# BelaCore.net
KiCad netlist of a schematic drawn in EAGLE
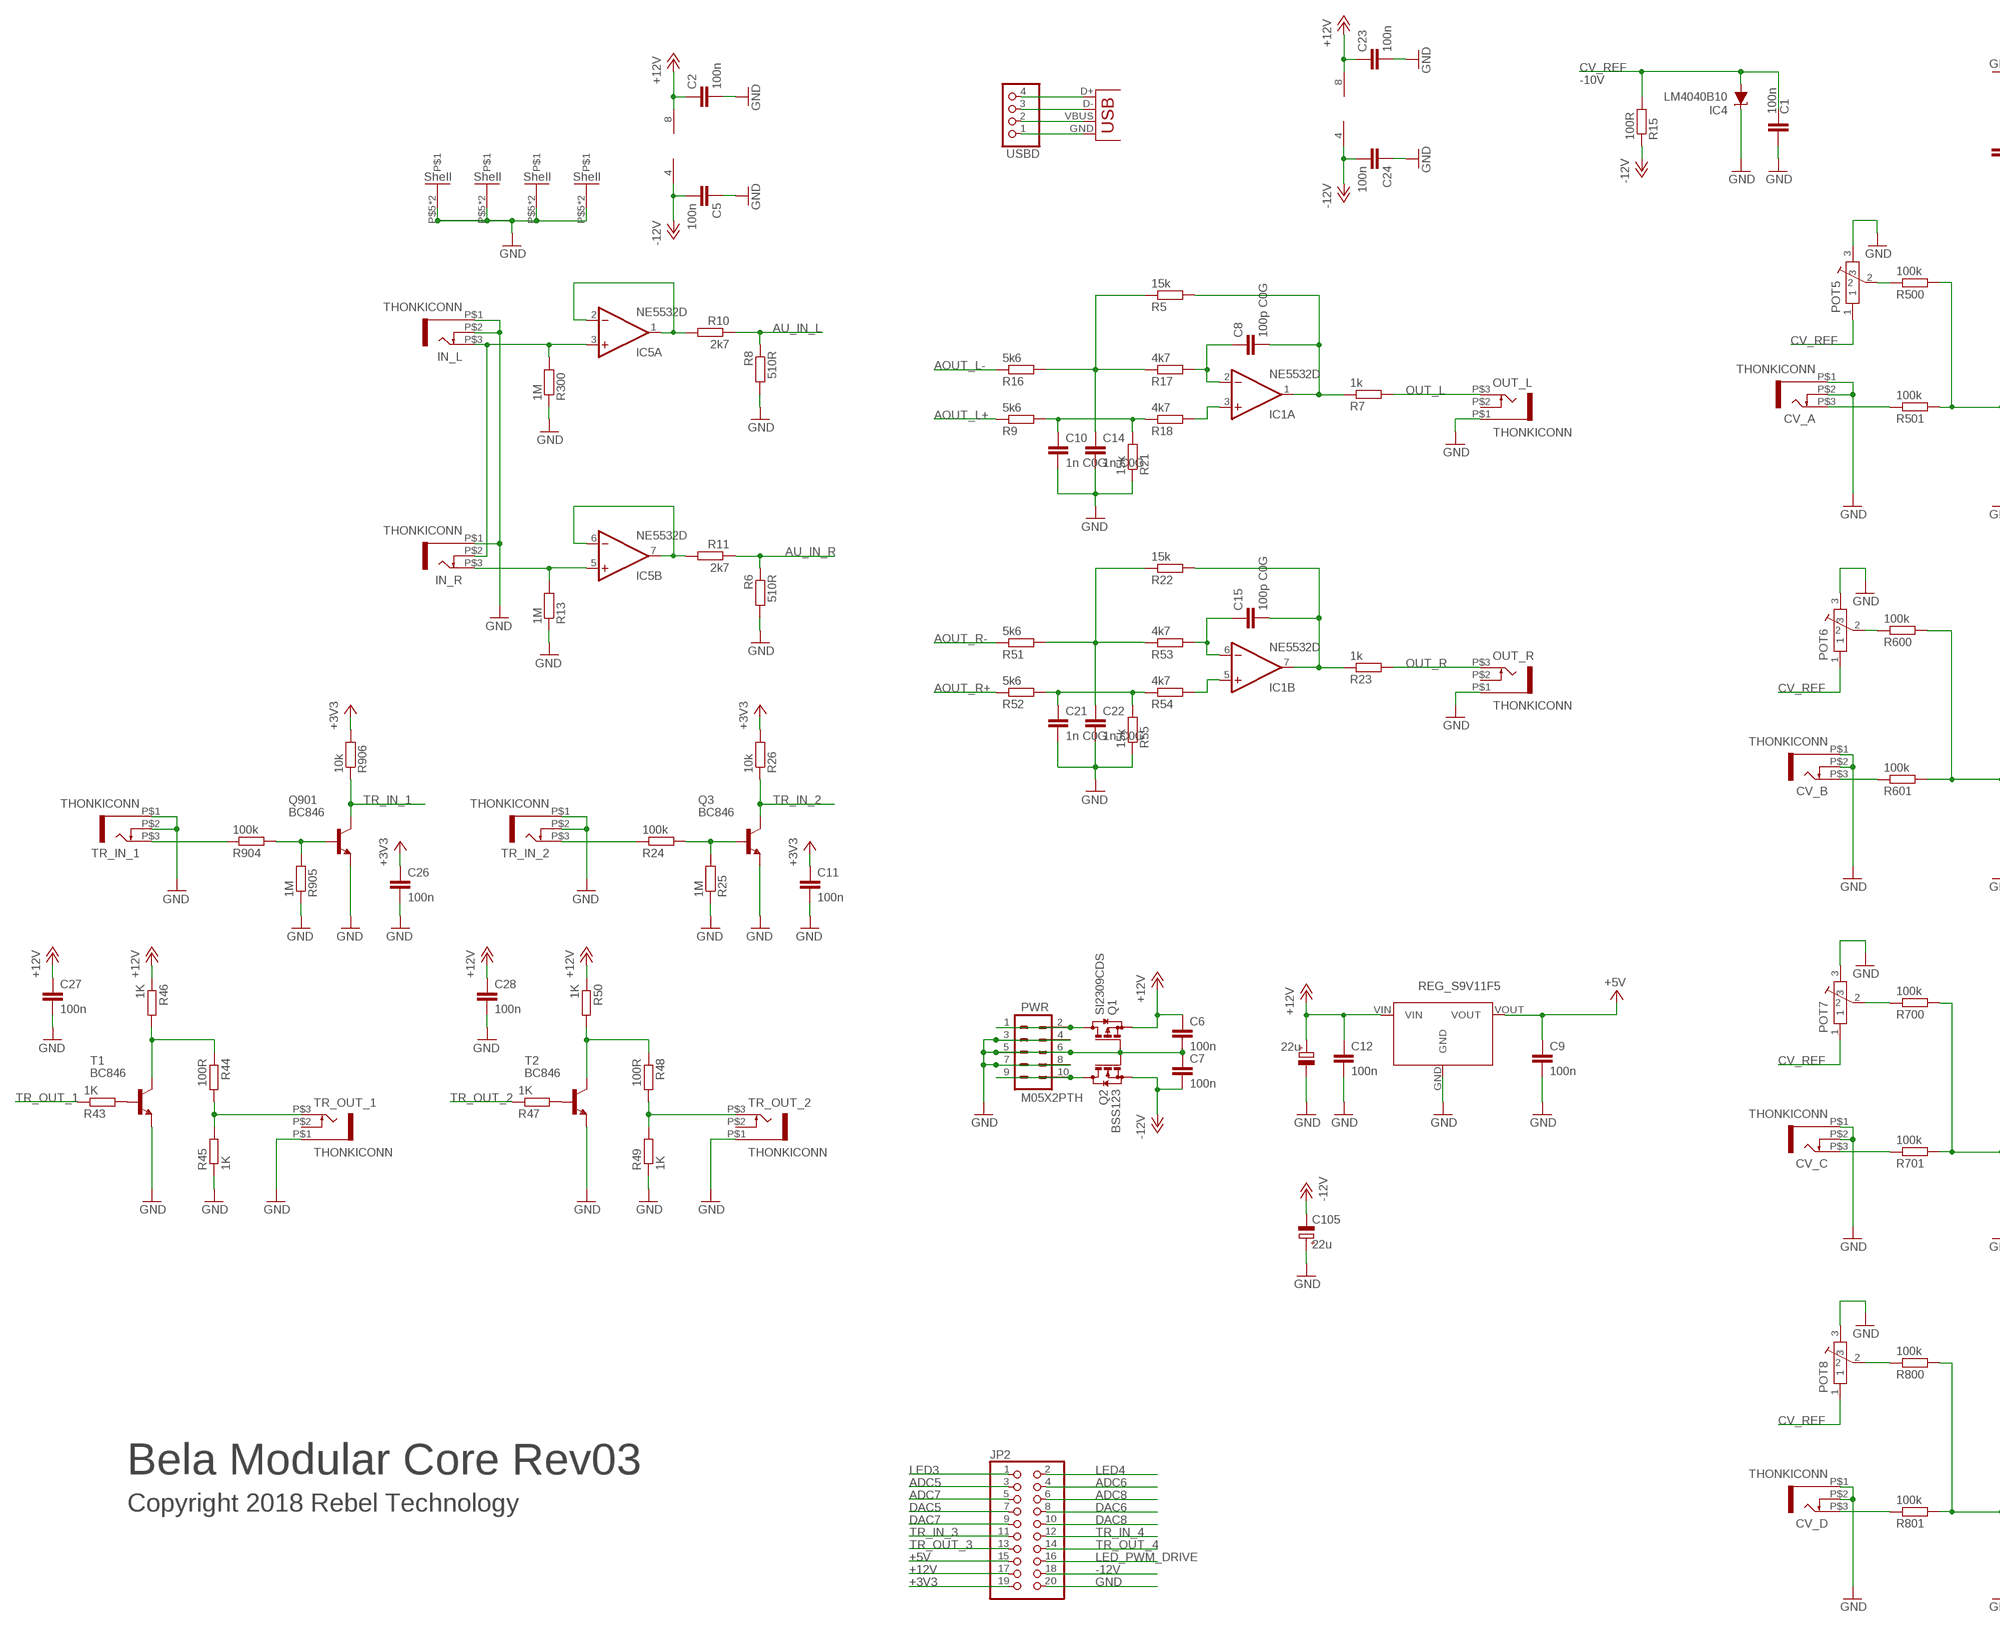
[diagram p0: schematic, sheet 1, part 1 of 2]
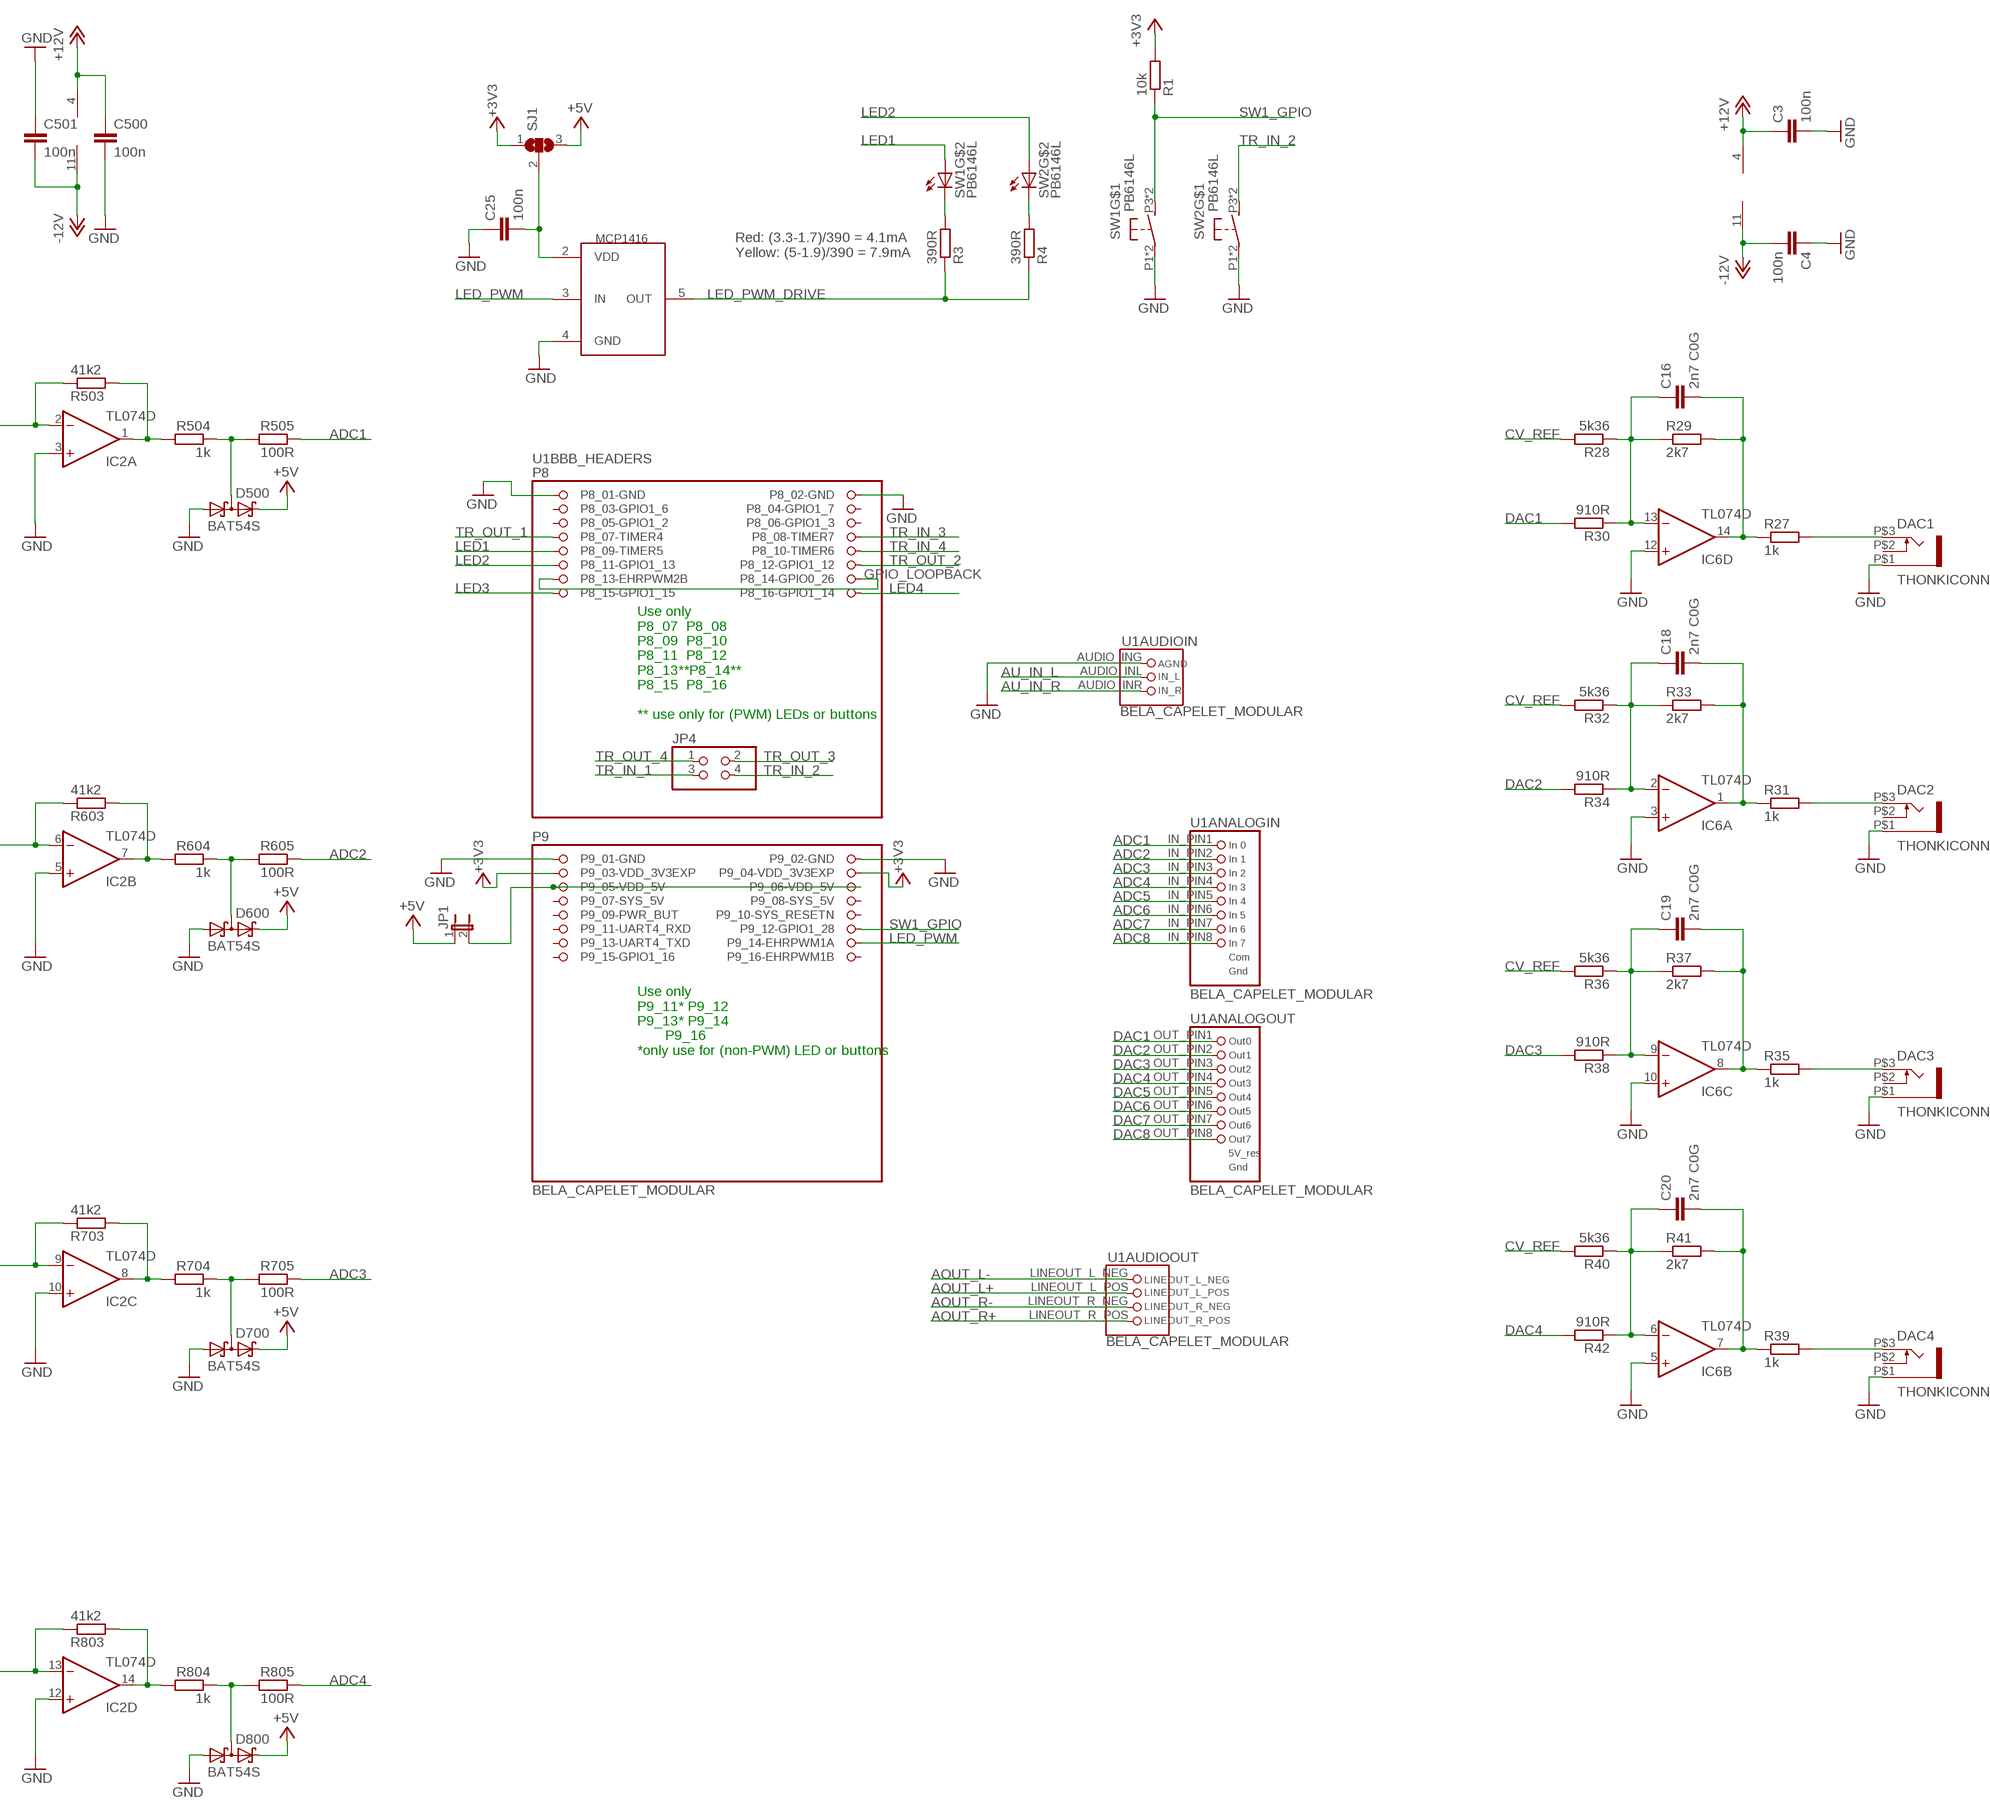
[diagram p1: schematic, sheet 1, part 2 of 2]

(export (version "E")
  (design (tool "Eeschema 10.0.6"))
  (components
    (comp (ref "C1")
      (value "100n")
      (footprint "eagle-import:C0603")
      (libsource (lib "eagle-import") (part "resistor_C-EUC0603"))
    )
    (comp (ref "C2")
      (value "100n")
      (footprint "eagle-import:C0603")
      (libsource (lib "eagle-import") (part "resistor_C-EUC0603"))
    )
    (comp (ref "C3")
      (value "100n")
      (footprint "eagle-import:C0603")
      (libsource (lib "eagle-import") (part "resistor_C-EUC0603"))
    )
    (comp (ref "C4")
      (value "100n")
      (footprint "eagle-import:C0603")
      (libsource (lib "eagle-import") (part "resistor_C-EUC0603"))
    )
    (comp (ref "C5")
      (value "100n")
      (footprint "eagle-import:C0603")
      (libsource (lib "eagle-import") (part "resistor_C-EUC0603"))
    )
    (comp (ref "C6")
      (value "100n")
      (footprint "eagle-import:C0603")
      (libsource (lib "eagle-import") (part "resistor_C-EUC0603"))
    )
    (comp (ref "C7")
      (value "100n")
      (footprint "eagle-import:C0603")
      (libsource (lib "eagle-import") (part "resistor_C-EUC0603"))
    )
    (comp (ref "C8")
      (value "100p C0G")
      (footprint "eagle-import:C0603")
      (libsource (lib "eagle-import") (part "resistor_C-EUC0603"))
    )
    (comp (ref "C9")
      (value "100n")
      (footprint "eagle-import:C0603")
      (libsource (lib "eagle-import") (part "C-EUC0603"))
    )
    (comp (ref "C10")
      (value "1n C0G")
      (footprint "eagle-import:C0603")
      (libsource (lib "eagle-import") (part "resistor_C-EUC0603"))
    )
    (comp (ref "C11")
      (value "100n")
      (footprint "eagle-import:C0603")
      (libsource (lib "eagle-import") (part "resistor_C-EUC0603"))
    )
    (comp (ref "C12")
      (value "100n")
      (footprint "eagle-import:C0603")
      (libsource (lib "eagle-import") (part "C-EUC0603"))
    )
    (comp (ref "C14")
      (value "1n C0G")
      (footprint "eagle-import:C0603")
      (libsource (lib "eagle-import") (part "resistor_C-EUC0603"))
    )
    (comp (ref "C15")
      (value "100p C0G")
      (footprint "eagle-import:C0603")
      (libsource (lib "eagle-import") (part "resistor_C-EUC0603"))
    )
    (comp (ref "C16")
      (value "2n7 C0G")
      (footprint "eagle-import:C0603")
      (libsource (lib "eagle-import") (part "C-EUC0603"))
    )
    (comp (ref "C17")
      (value "22u")
      (footprint "eagle-import:CPOL-5")
      (libsource (lib "eagle-import") (part "CPOL-EU153CLV-0505"))
    )
    (comp (ref "C18")
      (value "2n7 C0G")
      (footprint "eagle-import:C0603")
      (libsource (lib "eagle-import") (part "C-EUC0603"))
    )
    (comp (ref "C19")
      (value "2n7 C0G")
      (footprint "eagle-import:C0603")
      (libsource (lib "eagle-import") (part "C-EUC0603"))
    )
    (comp (ref "C20")
      (value "2n7 C0G")
      (footprint "eagle-import:C0603")
      (libsource (lib "eagle-import") (part "C-EUC0603"))
    )
    (comp (ref "C21")
      (value "1n C0G")
      (footprint "eagle-import:C0603")
      (libsource (lib "eagle-import") (part "resistor_C-EUC0603"))
    )
    (comp (ref "C22")
      (value "1n C0G")
      (footprint "eagle-import:C0603")
      (libsource (lib "eagle-import") (part "resistor_C-EUC0603"))
    )
    (comp (ref "C23")
      (value "100n")
      (footprint "eagle-import:C0603")
      (libsource (lib "eagle-import") (part "resistor_C-EUC0603"))
    )
    (comp (ref "C24")
      (value "100n")
      (footprint "eagle-import:C0603")
      (libsource (lib "eagle-import") (part "resistor_C-EUC0603"))
    )
    (comp (ref "C25")
      (value "100n")
      (footprint "eagle-import:C0603")
      (libsource (lib "eagle-import") (part "C-EUC0603"))
    )
    (comp (ref "C26")
      (value "100n")
      (footprint "eagle-import:C0603")
      (libsource (lib "eagle-import") (part "resistor_C-EUC0603"))
    )
    (comp (ref "C27")
      (value "100n")
      (footprint "eagle-import:C0603")
      (libsource (lib "eagle-import") (part "resistor_C-EUC0603"))
    )
    (comp (ref "C28")
      (value "100n")
      (footprint "eagle-import:C0603")
      (libsource (lib "eagle-import") (part "resistor_C-EUC0603"))
    )
    (comp (ref "C105")
      (value "22u")
      (footprint "eagle-import:CPOL-5")
      (libsource (lib "eagle-import") (part "CPOL-EU153CLV-0505"))
    )
    (comp (ref "C500")
      (value "100n")
      (footprint "eagle-import:C0603")
      (libsource (lib "eagle-import") (part "resistor_C-EUC0603"))
    )
    (comp (ref "C501")
      (value "100n")
      (footprint "eagle-import:C0603")
      (libsource (lib "eagle-import") (part "resistor_C-EUC0603"))
    )
    (comp (ref "CV_A")
      (value "THONKICONN")
      (footprint "eagle-import:THONKICONN")
      (libsource (lib "eagle-import") (part "THONKICONN"))
    )
    (comp (ref "CV_B")
      (value "THONKICONN")
      (footprint "eagle-import:THONKICONN")
      (libsource (lib "eagle-import") (part "THONKICONN"))
    )
    (comp (ref "CV_C")
      (value "THONKICONN")
      (footprint "eagle-import:THONKICONN")
      (libsource (lib "eagle-import") (part "THONKICONN"))
    )
    (comp (ref "CV_D")
      (value "THONKICONN")
      (footprint "eagle-import:THONKICONN")
      (libsource (lib "eagle-import") (part "THONKICONN"))
    )
    (comp (ref "D500")
      (value "BAT54S")
      (footprint "eagle-import:SOT23")
      (libsource (lib "eagle-import") (part "BAT54S"))
    )
    (comp (ref "D600")
      (value "BAT54S")
      (footprint "eagle-import:SOT23")
      (libsource (lib "eagle-import") (part "BAT54S"))
    )
    (comp (ref "D700")
      (value "BAT54S")
      (footprint "eagle-import:SOT23")
      (libsource (lib "eagle-import") (part "BAT54S"))
    )
    (comp (ref "D800")
      (value "BAT54S")
      (footprint "eagle-import:SOT23")
      (libsource (lib "eagle-import") (part "BAT54S"))
    )
    (comp (ref "DAC1")
      (value "THONKICONN")
      (footprint "eagle-import:THONKICONN")
      (libsource (lib "eagle-import") (part "THONKICONN"))
    )
    (comp (ref "DAC2")
      (value "THONKICONN")
      (footprint "eagle-import:THONKICONN")
      (libsource (lib "eagle-import") (part "THONKICONN"))
    )
    (comp (ref "DAC3")
      (value "THONKICONN")
      (footprint "eagle-import:THONKICONN")
      (libsource (lib "eagle-import") (part "THONKICONN"))
    )
    (comp (ref "DAC4")
      (value "THONKICONN")
      (footprint "eagle-import:THONKICONN")
      (libsource (lib "eagle-import") (part "THONKICONN"))
    )
    (comp (ref "IC1")
      (value "NE5532D")
      (footprint "eagle-import:SO08")
      (libsource (lib "eagle-import") (part "NE5532D"))
    )
    (comp (ref "IC2")
      (value "TL074D")
      (footprint "eagle-import:SO14")
      (libsource (lib "eagle-import") (part "TL074D"))
    )
    (comp (ref "IC4")
      (value "LM4040B10")
      (footprint "eagle-import:DBZ_R-PDSO-G3")
      (fields (field (name "MF") "TEXAS INSTRUMENT CONNECTORS") (field (name "MPN") "LM4041C12QDBZT"))
      (libsource (lib "eagle-import") (part "LM4041DBZC12"))
    )
    (comp (ref "IC5")
      (value "NE5532D")
      (footprint "eagle-import:SO08")
      (libsource (lib "eagle-import") (part "NE5532D"))
    )
    (comp (ref "IC6")
      (value "TL074D")
      (footprint "eagle-import:SO14")
      (libsource (lib "eagle-import") (part "TL074D"))
    )
    (comp (ref "IN_L")
      (value "THONKICONN")
      (footprint "eagle-import:THONKICONN")
      (libsource (lib "eagle-import") (part "THONKICONN"))
    )
    (comp (ref "IN_R")
      (value "THONKICONN")
      (footprint "eagle-import:THONKICONN")
      (libsource (lib "eagle-import") (part "THONKICONN"))
    )
    (comp (ref "JP1")
      (value "JUMPER-2PTH")
      (footprint "eagle-import:1X02")
      (libsource (lib "eagle-import") (part "JUMPER-2PTH"))
    )
    (comp (ref "JP2")
      (value "PINHD-2X10")
      (footprint "eagle-import:2X10")
      (libsource (lib "eagle-import") (part "PINHD-2X10"))
    )
    (comp (ref "JP4")
      (value "PINHD-2X02_2.54-SMD")
      (footprint "eagle-import:2X02SMD")
      (libsource (lib "eagle-import") (part "PINHD-2X02_2.54-SMD"))
    )
    (comp (ref "OUT_L")
      (value "THONKICONN")
      (footprint "eagle-import:THONKICONN")
      (libsource (lib "eagle-import") (part "THONKICONN"))
    )
    (comp (ref "OUT_R")
      (value "THONKICONN")
      (footprint "eagle-import:THONKICONN")
      (libsource (lib "eagle-import") (part "THONKICONN"))
    )
    (comp (ref "POT5")
      (value "POT-ALPS-RK09L1140")
      (footprint "eagle-import:POT-ALPS-RK09L1140")
      (libsource (lib "eagle-import") (part "POT-ALPS-RK09L1140"))
    )
    (comp (ref "POT6")
      (value "POT-ALPS-RK09L1140")
      (footprint "eagle-import:POT-ALPS-RK09L1140")
      (libsource (lib "eagle-import") (part "POT-ALPS-RK09L1140"))
    )
    (comp (ref "POT7")
      (value "POT-ALPS-RK09L1140")
      (footprint "eagle-import:POT-ALPS-RK09L1140")
      (libsource (lib "eagle-import") (part "POT-ALPS-RK09L1140"))
    )
    (comp (ref "POT8")
      (value "POT-ALPS-RK09L1140")
      (footprint "eagle-import:POT-ALPS-RK09L1140")
      (libsource (lib "eagle-import") (part "POT-ALPS-RK09L1140"))
    )
    (comp (ref "PWR")
      (value "M05X2PTH")
      (footprint "eagle-import:AVR_ICSP")
      (libsource (lib "eagle-import") (part "M05X2PTH"))
    )
    (comp (ref "Q1")
      (value "SI2309CDS")
      (footprint "eagle-import:SOT23")
      (libsource (lib "eagle-import") (part "BSS84"))
    )
    (comp (ref "Q2")
      (value "BSS123")
      (footprint "eagle-import:SOT23")
      (libsource (lib "eagle-import") (part "BSS123"))
    )
    (comp (ref "Q3")
      (value "BC846")
      (footprint "eagle-import:SOT23")
      (libsource (lib "eagle-import") (part "BC846"))
    )
    (comp (ref "Q901")
      (value "BC846")
      (footprint "eagle-import:SOT23")
      (libsource (lib "eagle-import") (part "BC846"))
    )
    (comp (ref "R1")
      (value "10k")
      (footprint "eagle-import:0603")
      (libsource (lib "eagle-import") (part "R-EU_0603"))
    )
    (comp (ref "R3")
      (value "390R")
      (footprint "eagle-import:0603")
      (libsource (lib "eagle-import") (part "R-EU_0603"))
    )
    (comp (ref "R4")
      (value "390R")
      (footprint "eagle-import:0603")
      (libsource (lib "eagle-import") (part "R-EU_0603"))
    )
    (comp (ref "R5")
      (value "15k")
      (footprint "eagle-import:0603")
      (libsource (lib "eagle-import") (part "R-EU_0603"))
    )
    (comp (ref "R6")
      (value "510R")
      (footprint "eagle-import:0603")
      (libsource (lib "eagle-import") (part "R-EU_0603"))
    )
    (comp (ref "R7")
      (value "1k")
      (footprint "eagle-import:0603")
      (libsource (lib "eagle-import") (part "R-EU_0603"))
    )
    (comp (ref "R8")
      (value "510R")
      (footprint "eagle-import:0603")
      (libsource (lib "eagle-import") (part "R-EU_0603"))
    )
    (comp (ref "R9")
      (value "5k6")
      (footprint "eagle-import:0603")
      (libsource (lib "eagle-import") (part "R-EU_0603"))
    )
    (comp (ref "R10")
      (value "2k7")
      (footprint "eagle-import:0603")
      (libsource (lib "eagle-import") (part "R-EU_0603"))
    )
    (comp (ref "R11")
      (value "2k7")
      (footprint "eagle-import:0603")
      (libsource (lib "eagle-import") (part "R-EU_0603"))
    )
    (comp (ref "R13")
      (value "1M")
      (footprint "eagle-import:0603")
      (libsource (lib "eagle-import") (part "R-EU_0603"))
    )
    (comp (ref "R15")
      (value "100R")
      (footprint "eagle-import:0603")
      (libsource (lib "eagle-import") (part "R-EU_0603"))
    )
    (comp (ref "R16")
      (value "5k6")
      (footprint "eagle-import:0603")
      (libsource (lib "eagle-import") (part "R-EU_0603"))
    )
    (comp (ref "R17")
      (value "4k7")
      (footprint "eagle-import:0603")
      (libsource (lib "eagle-import") (part "R-EU_0603"))
    )
    (comp (ref "R18")
      (value "4k7")
      (footprint "eagle-import:0603")
      (libsource (lib "eagle-import") (part "R-EU_0603"))
    )
    (comp (ref "R21")
      (value "15k")
      (footprint "eagle-import:0603")
      (libsource (lib "eagle-import") (part "R-EU_0603"))
    )
    (comp (ref "R22")
      (value "15k")
      (footprint "eagle-import:0603")
      (libsource (lib "eagle-import") (part "R-EU_0603"))
    )
    (comp (ref "R23")
      (value "1k")
      (footprint "eagle-import:0603")
      (libsource (lib "eagle-import") (part "R-EU_0603"))
    )
    (comp (ref "R24")
      (value "100k")
      (footprint "eagle-import:0603")
      (libsource (lib "eagle-import") (part "R-EU_0603"))
    )
    (comp (ref "R25")
      (value "1M")
      (footprint "eagle-import:0603")
      (libsource (lib "eagle-import") (part "R-EU_0603"))
    )
    (comp (ref "R26")
      (value "10k")
      (footprint "eagle-import:0603")
      (libsource (lib "eagle-import") (part "R-EU_0603"))
    )
    (comp (ref "R27")
      (value "1k")
      (footprint "eagle-import:0603")
      (libsource (lib "eagle-import") (part "R-EU_0603"))
    )
    (comp (ref "R28")
      (value "5k36")
      (footprint "eagle-import:0603")
      (libsource (lib "eagle-import") (part "R-EU_0603"))
    )
    (comp (ref "R29")
      (value "2k7")
      (footprint "eagle-import:0603")
      (libsource (lib "eagle-import") (part "R-EU_0603"))
    )
    (comp (ref "R30")
      (value "910R")
      (footprint "eagle-import:0603")
      (libsource (lib "eagle-import") (part "R-EU_0603"))
    )
    (comp (ref "R31")
      (value "1k")
      (footprint "eagle-import:0603")
      (libsource (lib "eagle-import") (part "R-EU_0603"))
    )
    (comp (ref "R32")
      (value "5k36")
      (footprint "eagle-import:0603")
      (libsource (lib "eagle-import") (part "R-EU_0603"))
    )
    (comp (ref "R33")
      (value "2k7")
      (footprint "eagle-import:0603")
      (libsource (lib "eagle-import") (part "R-EU_0603"))
    )
    (comp (ref "R34")
      (value "910R")
      (footprint "eagle-import:0603")
      (libsource (lib "eagle-import") (part "R-EU_0603"))
    )
    (comp (ref "R35")
      (value "1k")
      (footprint "eagle-import:0603")
      (libsource (lib "eagle-import") (part "R-EU_0603"))
    )
    (comp (ref "R36")
      (value "5k36")
      (footprint "eagle-import:0603")
      (libsource (lib "eagle-import") (part "R-EU_0603"))
    )
    (comp (ref "R37")
      (value "2k7")
      (footprint "eagle-import:0603")
      (libsource (lib "eagle-import") (part "R-EU_0603"))
    )
    (comp (ref "R38")
      (value "910R")
      (footprint "eagle-import:0603")
      (libsource (lib "eagle-import") (part "R-EU_0603"))
    )
    (comp (ref "R39")
      (value "1k")
      (footprint "eagle-import:0603")
      (libsource (lib "eagle-import") (part "R-EU_0603"))
    )
    (comp (ref "R40")
      (value "5k36")
      (footprint "eagle-import:0603")
      (libsource (lib "eagle-import") (part "R-EU_0603"))
    )
    (comp (ref "R41")
      (value "2k7")
      (footprint "eagle-import:0603")
      (libsource (lib "eagle-import") (part "R-EU_0603"))
    )
    (comp (ref "R42")
      (value "910R")
      (footprint "eagle-import:0603")
      (libsource (lib "eagle-import") (part "R-EU_0603"))
    )
    (comp (ref "R43")
      (value "1K")
      (footprint "eagle-import:0603")
      (libsource (lib "eagle-import") (part "R-EU_0603"))
    )
    (comp (ref "R44")
      (value "100R")
      (footprint "eagle-import:0603")
      (libsource (lib "eagle-import") (part "R-EU_0603"))
    )
    (comp (ref "R45")
      (value "1K")
      (footprint "eagle-import:0603")
      (libsource (lib "eagle-import") (part "R-EU_0603"))
    )
    (comp (ref "R46")
      (value "1K")
      (footprint "eagle-import:0603")
      (libsource (lib "eagle-import") (part "R-EU_0603"))
    )
    (comp (ref "R47")
      (value "1K")
      (footprint "eagle-import:0603")
      (libsource (lib "eagle-import") (part "R-EU_0603"))
    )
    (comp (ref "R48")
      (value "100R")
      (footprint "eagle-import:0603")
      (libsource (lib "eagle-import") (part "R-EU_0603"))
    )
    (comp (ref "R49")
      (value "1K")
      (footprint "eagle-import:0603")
      (libsource (lib "eagle-import") (part "R-EU_0603"))
    )
    (comp (ref "R50")
      (value "1K")
      (footprint "eagle-import:0603")
      (libsource (lib "eagle-import") (part "R-EU_0603"))
    )
    (comp (ref "R51")
      (value "5k6")
      (footprint "eagle-import:0603")
      (libsource (lib "eagle-import") (part "R-EU_0603"))
    )
    (comp (ref "R52")
      (value "5k6")
      (footprint "eagle-import:0603")
      (libsource (lib "eagle-import") (part "R-EU_0603"))
    )
    (comp (ref "R53")
      (value "4k7")
      (footprint "eagle-import:0603")
      (libsource (lib "eagle-import") (part "R-EU_0603"))
    )
    (comp (ref "R54")
      (value "4k7")
      (footprint "eagle-import:0603")
      (libsource (lib "eagle-import") (part "R-EU_0603"))
    )
    (comp (ref "R55")
      (value "15k")
      (footprint "eagle-import:0603")
      (libsource (lib "eagle-import") (part "R-EU_0603"))
    )
    (comp (ref "R300")
      (value "1M")
      (footprint "eagle-import:0603")
      (libsource (lib "eagle-import") (part "R-EU_0603"))
    )
    (comp (ref "R500")
      (value "100k")
      (footprint "eagle-import:0603")
      (libsource (lib "eagle-import") (part "R-EU_0603"))
    )
    (comp (ref "R501")
      (value "100k")
      (footprint "eagle-import:0603")
      (libsource (lib "eagle-import") (part "R-EU_0603"))
    )
    (comp (ref "R503")
      (value "41k2")
      (footprint "eagle-import:0603")
      (libsource (lib "eagle-import") (part "R-EU_0603"))
    )
    (comp (ref "R504")
      (value "1k")
      (footprint "eagle-import:0603")
      (libsource (lib "eagle-import") (part "R-EU_0603"))
    )
    (comp (ref "R505")
      (value "100R")
      (footprint "eagle-import:0603")
      (libsource (lib "eagle-import") (part "R-EU_0603"))
    )
    (comp (ref "R600")
      (value "100k")
      (footprint "eagle-import:0603")
      (libsource (lib "eagle-import") (part "R-EU_0603"))
    )
    (comp (ref "R601")
      (value "100k")
      (footprint "eagle-import:0603")
      (libsource (lib "eagle-import") (part "R-EU_0603"))
    )
    (comp (ref "R603")
      (value "41k2")
      (footprint "eagle-import:0603")
      (libsource (lib "eagle-import") (part "R-EU_0603"))
    )
    (comp (ref "R604")
      (value "1k")
      (footprint "eagle-import:0603")
      (libsource (lib "eagle-import") (part "R-EU_0603"))
    )
    (comp (ref "R605")
      (value "100R")
      (footprint "eagle-import:0603")
      (libsource (lib "eagle-import") (part "R-EU_0603"))
    )
    (comp (ref "R700")
      (value "100k")
      (footprint "eagle-import:0603")
      (libsource (lib "eagle-import") (part "R-EU_0603"))
    )
    (comp (ref "R701")
      (value "100k")
      (footprint "eagle-import:0603")
      (libsource (lib "eagle-import") (part "R-EU_0603"))
    )
    (comp (ref "R703")
      (value "41k2")
      (footprint "eagle-import:0603")
      (libsource (lib "eagle-import") (part "R-EU_0603"))
    )
    (comp (ref "R704")
      (value "1k")
      (footprint "eagle-import:0603")
      (libsource (lib "eagle-import") (part "R-EU_0603"))
    )
    (comp (ref "R705")
      (value "100R")
      (footprint "eagle-import:0603")
      (libsource (lib "eagle-import") (part "R-EU_0603"))
    )
    (comp (ref "R800")
      (value "100k")
      (footprint "eagle-import:0603")
      (libsource (lib "eagle-import") (part "R-EU_0603"))
    )
    (comp (ref "R801")
      (value "100k")
      (footprint "eagle-import:0603")
      (libsource (lib "eagle-import") (part "R-EU_0603"))
    )
    (comp (ref "R803")
      (value "41k2")
      (footprint "eagle-import:0603")
      (libsource (lib "eagle-import") (part "R-EU_0603"))
    )
    (comp (ref "R804")
      (value "1k")
      (footprint "eagle-import:0603")
      (libsource (lib "eagle-import") (part "R-EU_0603"))
    )
    (comp (ref "R805")
      (value "100R")
      (footprint "eagle-import:0603")
      (libsource (lib "eagle-import") (part "R-EU_0603"))
    )
    (comp (ref "R904")
      (value "100k")
      (footprint "eagle-import:0603")
      (libsource (lib "eagle-import") (part "R-EU_0603"))
    )
    (comp (ref "R905")
      (value "1M")
      (footprint "eagle-import:0603")
      (libsource (lib "eagle-import") (part "R-EU_0603"))
    )
    (comp (ref "R906")
      (value "10k")
      (footprint "eagle-import:0603")
      (libsource (lib "eagle-import") (part "R-EU_0603"))
    )
    (comp (ref "SJ1")
      (value "SJ2W")
      (footprint "eagle-import:SJ_2")
      (libsource (lib "eagle-import") (part "SJ2W"))
    )
    (comp (ref "SW1")
      (value "PB6146L")
      (footprint "eagle-import:PB6146L")
      (libsource (lib "eagle-import") (part "PB6146L"))
    )
    (comp (ref "SW2")
      (value "PB6146L")
      (footprint "eagle-import:PB6146L")
      (libsource (lib "eagle-import") (part "PB6146L"))
    )
    (comp (ref "T1")
      (value "BC846")
      (footprint "eagle-import:SOT23")
      (libsource (lib "eagle-import") (part "BC846"))
    )
    (comp (ref "T2")
      (value "BC846")
      (footprint "eagle-import:SOT23")
      (libsource (lib "eagle-import") (part "BC846"))
    )
    (comp (ref "TR_IN_1")
      (value "THONKICONN")
      (footprint "eagle-import:THONKICONN")
      (libsource (lib "eagle-import") (part "THONKICONN"))
    )
    (comp (ref "TR_IN_2")
      (value "THONKICONN")
      (footprint "eagle-import:THONKICONN")
      (libsource (lib "eagle-import") (part "THONKICONN"))
    )
    (comp (ref "TR_OUT_1")
      (value "THONKICONN")
      (footprint "eagle-import:THONKICONN")
      (libsource (lib "eagle-import") (part "THONKICONN"))
    )
    (comp (ref "TR_OUT_2")
      (value "THONKICONN")
      (footprint "eagle-import:THONKICONN")
      (libsource (lib "eagle-import") (part "THONKICONN"))
    )
    (comp (ref "U1")
      (value "BELA_CAPELET_MODULAR")
      (footprint "eagle-import:BELA_CAPELET_MODULAR")
      (libsource (lib "eagle-import") (part "BELA_CAPELET_MODULAR"))
    )
    (comp (ref "U2")
      (value "MCP1416")
      (footprint "eagle-import:SOT23-5")
      (libsource (lib "eagle-import") (part "MCP1416"))
    )
    (comp (ref "U3")
      (value "REG_S9V11F5")
      (footprint "eagle-import:REG_S9V11F5")
      (libsource (lib "eagle-import") (part "REG_S9V11F5"))
    )
    (comp (ref "USBD")
      (value "PINHD-1X4")
      (footprint "eagle-import:1X04")
      (libsource (lib "eagle-import") (part "PINHD-1X4"))
    )
    (comp (ref "X1")
      (value "USBPTH-VERTICAL")
      (footprint "eagle-import:USB-B-PTH-VERTICAL")
      (libsource (lib "eagle-import") (part "USBPTH-VERTICAL"))
    )
  )
  (nets
    (net (code "1") (name "+3V3") (class "Default")
      (node (ref "C11") (pin "1") (pinfunction "1_1") (pintype "passive"))
      (node (ref "C26") (pin "1") (pinfunction "1_1") (pintype "passive"))
      (node (ref "JP2") (pin "19") (pinfunction "19_19") (pintype "passive"))
      (node (ref "R1") (pin "2") (pinfunction "2_2") (pintype "passive"))
      (node (ref "R26") (pin "2") (pinfunction "2_2") (pintype "passive"))
      (node (ref "R906") (pin "2") (pinfunction "2_2") (pintype "passive"))
      (node (ref "SJ1") (pin "1") (pinfunction "1_1") (pintype "passive"))
      (node (ref "U1") (pin "P9_03") (pinfunction "P9_03-VDD_3V3EXP_P9_03") (pintype "power_in"))
      (node (ref "U1") (pin "P9_04") (pinfunction "P9_04-VDD_3V3EXP_P9_04") (pintype "power_in"))
    )
    (net (code "2") (name "+5V") (class "Default")
      (node (ref "C9") (pin "1") (pinfunction "1_1") (pintype "passive"))
      (node (ref "D500") (pin "2") (pinfunction "C2_2") (pintype "passive"))
      (node (ref "D600") (pin "2") (pinfunction "C2_2") (pintype "passive"))
      (node (ref "D700") (pin "2") (pinfunction "C2_2") (pintype "passive"))
      (node (ref "D800") (pin "2") (pinfunction "C2_2") (pintype "passive"))
      (node (ref "JP1") (pin "1") (pinfunction "1_1") (pintype "passive"))
      (node (ref "JP2") (pin "15") (pinfunction "15_15") (pintype "passive"))
      (node (ref "SJ1") (pin "3") (pinfunction "3_3") (pintype "passive"))
      (node (ref "U3") (pin "VOUT") (pinfunction "VOUT_VOUT") (pintype "output"))
    )
    (net (code "3") (name "+12V") (class "Default")
      (node (ref "C12") (pin "1") (pinfunction "1_1") (pintype "passive"))
      (node (ref "C17") (pin "+") (pinfunction "+_+") (pintype "passive"))
      (node (ref "C2") (pin "1") (pinfunction "1_1") (pintype "passive"))
      (node (ref "C23") (pin "1") (pinfunction "1_1") (pintype "passive"))
      (node (ref "C27") (pin "1") (pinfunction "1_1") (pintype "passive"))
      (node (ref "C28") (pin "1") (pinfunction "1_1") (pintype "passive"))
      (node (ref "C3") (pin "1") (pinfunction "1_1") (pintype "passive"))
      (node (ref "C500") (pin "1") (pinfunction "1_1") (pintype "passive"))
      (node (ref "C6") (pin "1") (pinfunction "1_1") (pintype "passive"))
      (node (ref "IC1") (pin "8") (pinfunction "V+_8") (pintype "power_in"))
      (node (ref "IC2") (pin "4") (pinfunction "V+_4") (pintype "power_in"))
      (node (ref "IC5") (pin "8") (pinfunction "V+_8") (pintype "power_in"))
      (node (ref "IC6") (pin "4") (pinfunction "V+_4") (pintype "power_in"))
      (node (ref "JP2") (pin "17") (pinfunction "17_17") (pintype "passive"))
      (node (ref "Q1") (pin "2") (pinfunction "S_2") (pintype "passive"))
      (node (ref "R46") (pin "1") (pinfunction "1_1") (pintype "passive"))
      (node (ref "R50") (pin "1") (pinfunction "1_1") (pintype "passive"))
      (node (ref "U3") (pin "VIN") (pinfunction "VIN_VIN") (pintype "input"))
    )
    (net (code "4") (name "-12V") (class "Default")
      (node (ref "C105") (pin "-") (pinfunction "-_-") (pintype "passive"))
      (node (ref "C24") (pin "2") (pinfunction "2_2") (pintype "passive"))
      (node (ref "C4") (pin "2") (pinfunction "2_2") (pintype "passive"))
      (node (ref "C5") (pin "2") (pinfunction "2_2") (pintype "passive"))
      (node (ref "C501") (pin "2") (pinfunction "2_2") (pintype "passive"))
      (node (ref "C7") (pin "2") (pinfunction "2_2") (pintype "passive"))
      (node (ref "IC1") (pin "4") (pinfunction "V-_4") (pintype "power_in"))
      (node (ref "IC2") (pin "11") (pinfunction "V-_11") (pintype "power_in"))
      (node (ref "IC5") (pin "4") (pinfunction "V-_4") (pintype "power_in"))
      (node (ref "IC6") (pin "11") (pinfunction "V-_11") (pintype "power_in"))
      (node (ref "JP2") (pin "18") (pinfunction "18_18") (pintype "passive"))
      (node (ref "Q2") (pin "2") (pinfunction "S_2") (pintype "passive"))
      (node (ref "R15") (pin "1") (pinfunction "1_1") (pintype "passive"))
    )
    (net (code "5") (name "/ADC1") (class "Default")
      (node (ref "R505") (pin "1") (pinfunction "1_1") (pintype "passive"))
      (node (ref "U1") (pin "IN_PIN1") (pinfunction "1_IN_PIN1") (pintype "passive"))
    )
    (net (code "6") (name "/ADC2") (class "Default")
      (node (ref "R605") (pin "1") (pinfunction "1_1") (pintype "passive"))
      (node (ref "U1") (pin "IN_PIN2") (pinfunction "2_IN_PIN2") (pintype "passive"))
    )
    (net (code "7") (name "/ADC3") (class "Default")
      (node (ref "R705") (pin "1") (pinfunction "1_1") (pintype "passive"))
      (node (ref "U1") (pin "IN_PIN3") (pinfunction "3_IN_PIN3") (pintype "passive"))
    )
    (net (code "8") (name "/ADC4") (class "Default")
      (node (ref "R805") (pin "1") (pinfunction "1_1") (pintype "passive"))
      (node (ref "U1") (pin "IN_PIN4") (pinfunction "4_IN_PIN4") (pintype "passive"))
    )
    (net (code "9") (name "/ADC5") (class "Default")
      (node (ref "JP2") (pin "3") (pinfunction "3_3") (pintype "passive"))
      (node (ref "U1") (pin "IN_PIN5") (pinfunction "5_IN_PIN5") (pintype "passive"))
    )
    (net (code "10") (name "/ADC6") (class "Default")
      (node (ref "JP2") (pin "4") (pinfunction "4_4") (pintype "passive"))
      (node (ref "U1") (pin "IN_PIN6") (pinfunction "6_IN_PIN6") (pintype "passive"))
    )
    (net (code "11") (name "/ADC7") (class "Default")
      (node (ref "JP2") (pin "5") (pinfunction "5_5") (pintype "passive"))
      (node (ref "U1") (pin "IN_PIN7") (pinfunction "7_IN_PIN7") (pintype "passive"))
    )
    (net (code "12") (name "/ADC8") (class "Default")
      (node (ref "JP2") (pin "6") (pinfunction "6_6") (pintype "passive"))
      (node (ref "U1") (pin "IN_PIN8") (pinfunction "8_IN_PIN8") (pintype "passive"))
    )
    (net (code "13") (name "/AOUT_L+") (class "Default")
      (node (ref "R9") (pin "1") (pinfunction "1_1") (pintype "passive"))
      (node (ref "U1") (pin "LINEOUT_L_POS") (pinfunction "2_LINEOUT_L_POS") (pintype "passive"))
    )
    (net (code "14") (name "/AOUT_L-") (class "Default")
      (node (ref "R16") (pin "1") (pinfunction "1_1") (pintype "passive"))
      (node (ref "U1") (pin "LINEOUT_L_NEG") (pinfunction "1_LINEOUT_L_NEG") (pintype "passive"))
    )
    (net (code "15") (name "/AOUT_R+") (class "Default")
      (node (ref "R52") (pin "1") (pinfunction "1_1") (pintype "passive"))
      (node (ref "U1") (pin "LINEOUT_R_POS") (pinfunction "4_LINEOUT_R_POS") (pintype "passive"))
    )
    (net (code "16") (name "/AOUT_R-") (class "Default")
      (node (ref "R51") (pin "1") (pinfunction "1_1") (pintype "passive"))
      (node (ref "U1") (pin "LINEOUT_R_NEG") (pinfunction "3_LINEOUT_R_NEG") (pintype "passive"))
    )
    (net (code "17") (name "/AU_IN_L") (class "Default")
      (node (ref "R10") (pin "1") (pinfunction "1_1") (pintype "passive"))
      (node (ref "R8") (pin "1") (pinfunction "1_1") (pintype "passive"))
      (node (ref "U1") (pin "AUDIO_INL") (pinfunction "2_AUDIO_INL") (pintype "passive"))
    )
    (net (code "18") (name "/AU_IN_R") (class "Default")
      (node (ref "R11") (pin "1") (pinfunction "1_1") (pintype "passive"))
      (node (ref "R6") (pin "1") (pinfunction "1_1") (pintype "passive"))
      (node (ref "U1") (pin "AUDIO_INR") (pinfunction "3_AUDIO_INR") (pintype "passive"))
    )
    (net (code "19") (name "/CV_REF") (class "Default")
      (node (ref "C1") (pin "1") (pinfunction "1_1") (pintype "passive"))
      (node (ref "IC4") (pin "2") (pinfunction "A_2") (pintype "passive"))
      (node (ref "POT5") (pin "1") (pinfunction "1_1") (pintype "bidirectional"))
      (node (ref "POT6") (pin "1") (pinfunction "1_1") (pintype "bidirectional"))
      (node (ref "POT7") (pin "1") (pinfunction "1_1") (pintype "bidirectional"))
      (node (ref "POT8") (pin "1") (pinfunction "1_1") (pintype "bidirectional"))
      (node (ref "R15") (pin "2") (pinfunction "2_2") (pintype "passive"))
      (node (ref "R28") (pin "2") (pinfunction "2_2") (pintype "passive"))
      (node (ref "R32") (pin "2") (pinfunction "2_2") (pintype "passive"))
      (node (ref "R36") (pin "2") (pinfunction "2_2") (pintype "passive"))
      (node (ref "R40") (pin "2") (pinfunction "2_2") (pintype "passive"))
    )
    (net (code "20") (name "/DAC1") (class "Default")
      (node (ref "R30") (pin "2") (pinfunction "2_2") (pintype "passive"))
      (node (ref "U1") (pin "OUT_PIN1") (pinfunction "1_OUT_PIN1") (pintype "passive"))
    )
    (net (code "21") (name "/DAC2") (class "Default")
      (node (ref "R34") (pin "2") (pinfunction "2_2") (pintype "passive"))
      (node (ref "U1") (pin "OUT_PIN2") (pinfunction "2_OUT_PIN2") (pintype "passive"))
    )
    (net (code "22") (name "/DAC3") (class "Default")
      (node (ref "R38") (pin "2") (pinfunction "2_2") (pintype "passive"))
      (node (ref "U1") (pin "OUT_PIN3") (pinfunction "3_OUT_PIN3") (pintype "passive"))
    )
    (net (code "23") (name "/DAC4") (class "Default")
      (node (ref "R42") (pin "2") (pinfunction "2_2") (pintype "passive"))
      (node (ref "U1") (pin "OUT_PIN4") (pinfunction "4_OUT_PIN4") (pintype "passive"))
    )
    (net (code "24") (name "/DAC5") (class "Default")
      (node (ref "JP2") (pin "7") (pinfunction "7_7") (pintype "passive"))
      (node (ref "U1") (pin "OUT_PIN5") (pinfunction "5_OUT_PIN5") (pintype "passive"))
    )
    (net (code "25") (name "/DAC6") (class "Default")
      (node (ref "JP2") (pin "8") (pinfunction "8_8") (pintype "passive"))
      (node (ref "U1") (pin "OUT_PIN6") (pinfunction "6_OUT_PIN6") (pintype "passive"))
    )
    (net (code "26") (name "/DAC7") (class "Default")
      (node (ref "JP2") (pin "9") (pinfunction "9_9") (pintype "passive"))
      (node (ref "U1") (pin "OUT_PIN7") (pinfunction "7_OUT_PIN7") (pintype "passive"))
    )
    (net (code "27") (name "/DAC8") (class "Default")
      (node (ref "JP2") (pin "10") (pinfunction "10_10") (pintype "passive"))
      (node (ref "U1") (pin "OUT_PIN8") (pinfunction "8_OUT_PIN8") (pintype "passive"))
    )
    (net (code "28") (name "/GPIO_LOOPBACK") (class "Default")
      (node (ref "U1") (pin "P8_13") (pinfunction "P8_13-EHRPWM2B_P8_13") (pintype "passive"))
      (node (ref "U1") (pin "P8_14") (pinfunction "P8_14-GPIO0_26_P8_14") (pintype "passive"))
    )
    (net (code "29") (name "/LED1") (class "Default")
      (node (ref "SW1") (pin "PL1") (pinfunction "A_PL1") (pintype "passive"))
      (node (ref "U1") (pin "P8_09") (pinfunction "P8_09-TIMER5_P8_09") (pintype "passive"))
    )
    (net (code "30") (name "/LED2") (class "Default")
      (node (ref "SW2") (pin "PL1") (pinfunction "A_PL1") (pintype "passive"))
      (node (ref "U1") (pin "P8_11") (pinfunction "P8_11-GPIO1_13_P8_11") (pintype "passive"))
    )
    (net (code "31") (name "/LED3") (class "Default")
      (node (ref "JP2") (pin "1") (pinfunction "1_1") (pintype "passive"))
      (node (ref "U1") (pin "P8_15") (pinfunction "P8_15-GPIO1_15_P8_15") (pintype "passive"))
    )
    (net (code "32") (name "/LED4") (class "Default")
      (node (ref "JP2") (pin "2") (pinfunction "2_2") (pintype "passive"))
      (node (ref "U1") (pin "P8_16") (pinfunction "P8_16-GPIO1_14_P8_16") (pintype "passive"))
    )
    (net (code "33") (name "/LED_PWM") (class "Default")
      (node (ref "U1") (pin "P9_14") (pinfunction "P9_14-EHRPWM1A_P9_14") (pintype "passive"))
      (node (ref "U2") (pin "3") (pinfunction "IN_3") (pintype "bidirectional"))
    )
    (net (code "34") (name "/LED_PWM_DRIVE") (class "Default")
      (node (ref "JP2") (pin "16") (pinfunction "16_16") (pintype "passive"))
      (node (ref "R3") (pin "1") (pinfunction "1_1") (pintype "passive"))
      (node (ref "R4") (pin "1") (pinfunction "1_1") (pintype "passive"))
      (node (ref "U2") (pin "5") (pinfunction "OUT_5") (pintype "bidirectional"))
    )
    (net (code "35") (name "/OUT_L") (class "Default")
      (node (ref "OUT_L") (pin "P$3") (pinfunction "3_P$3") (pintype "passive"))
      (node (ref "R7") (pin "2") (pinfunction "2_2") (pintype "passive"))
    )
    (net (code "36") (name "/OUT_R") (class "Default")
      (node (ref "OUT_R") (pin "P$3") (pinfunction "3_P$3") (pintype "passive"))
      (node (ref "R23") (pin "2") (pinfunction "2_2") (pintype "passive"))
    )
    (net (code "37") (name "/P9_07-SYS_5V") (class "Default")
      (node (ref "U1") (pin "P9_07") (pinfunction "P9_07-SYS_5V_P9_07") (pintype "power_in"))
    )
    (net (code "38") (name "/SW1_GPIO") (class "Default")
      (node (ref "R1") (pin "1") (pinfunction "1_1") (pintype "passive"))
      (node (ref "SW1") (pin "P3") (pinfunction "S_P3") (pintype "passive"))
      (node (ref "SW1") (pin "P4") (pinfunction "S_P4") (pintype "passive"))
      (node (ref "U1") (pin "P9_12") (pinfunction "P9_12-GPIO1_28_P9_12") (pintype "passive"))
    )
    (net (code "39") (name "/TR_IN_1") (class "Default")
      (node (ref "JP4") (pin "3") (pinfunction "3_3") (pintype "passive"))
      (node (ref "Q901") (pin "3") (pinfunction "C_3") (pintype "passive"))
      (node (ref "R906") (pin "1") (pinfunction "1_1") (pintype "passive"))
    )
    (net (code "40") (name "/TR_IN_2") (class "Default")
      (node (ref "JP4") (pin "4") (pinfunction "4_4") (pintype "passive"))
      (node (ref "Q3") (pin "3") (pinfunction "C_3") (pintype "passive"))
      (node (ref "R26") (pin "1") (pinfunction "1_1") (pintype "passive"))
      (node (ref "SW2") (pin "P3") (pinfunction "S_P3") (pintype "passive"))
      (node (ref "SW2") (pin "P4") (pinfunction "S_P4") (pintype "passive"))
    )
    (net (code "41") (name "/TR_IN_3") (class "Default")
      (node (ref "JP2") (pin "11") (pinfunction "11_11") (pintype "passive"))
      (node (ref "U1") (pin "P8_08") (pinfunction "P8_08-TIMER7_P8_08") (pintype "passive"))
    )
    (net (code "42") (name "/TR_IN_4") (class "Default")
      (node (ref "JP2") (pin "12") (pinfunction "12_12") (pintype "passive"))
      (node (ref "U1") (pin "P8_10") (pinfunction "P8_10-TIMER6_P8_10") (pintype "passive"))
    )
    (net (code "43") (name "/TR_OUT_1") (class "Default")
      (node (ref "R43") (pin "1") (pinfunction "1_1") (pintype "passive"))
      (node (ref "U1") (pin "P8_07") (pinfunction "P8_07-TIMER4_P8_07") (pintype "passive"))
    )
    (net (code "44") (name "/TR_OUT_2") (class "Default")
      (node (ref "R47") (pin "1") (pinfunction "1_1") (pintype "passive"))
      (node (ref "U1") (pin "P8_12") (pinfunction "P8_12-GPIO1_12_P8_12") (pintype "passive"))
    )
    (net (code "45") (name "/TR_OUT_3") (class "Default")
      (node (ref "JP2") (pin "13") (pinfunction "13_13") (pintype "passive"))
      (node (ref "JP4") (pin "2") (pinfunction "2_2") (pintype "passive"))
    )
    (net (code "46") (name "/TR_OUT_4") (class "Default")
      (node (ref "JP2") (pin "14") (pinfunction "14_14") (pintype "passive"))
      (node (ref "JP4") (pin "1") (pinfunction "1_1") (pintype "passive"))
    )
    (net (code "47") (name "GND") (class "Default")
      (node (ref "C1") (pin "2") (pinfunction "2_2") (pintype "passive"))
      (node (ref "C10") (pin "2") (pinfunction "2_2") (pintype "passive"))
      (node (ref "C105") (pin "+") (pinfunction "+_+") (pintype "passive"))
      (node (ref "C11") (pin "2") (pinfunction "2_2") (pintype "passive"))
      (node (ref "C12") (pin "2") (pinfunction "2_2") (pintype "passive"))
      (node (ref "C14") (pin "2") (pinfunction "2_2") (pintype "passive"))
      (node (ref "C17") (pin "-") (pinfunction "-_-") (pintype "passive"))
      (node (ref "C2") (pin "2") (pinfunction "2_2") (pintype "passive"))
      (node (ref "C21") (pin "2") (pinfunction "2_2") (pintype "passive"))
      (node (ref "C22") (pin "2") (pinfunction "2_2") (pintype "passive"))
      (node (ref "C23") (pin "2") (pinfunction "2_2") (pintype "passive"))
      (node (ref "C24") (pin "1") (pinfunction "1_1") (pintype "passive"))
      (node (ref "C25") (pin "1") (pinfunction "1_1") (pintype "passive"))
      (node (ref "C26") (pin "2") (pinfunction "2_2") (pintype "passive"))
      (node (ref "C27") (pin "2") (pinfunction "2_2") (pintype "passive"))
      (node (ref "C28") (pin "2") (pinfunction "2_2") (pintype "passive"))
      (node (ref "C3") (pin "2") (pinfunction "2_2") (pintype "passive"))
      (node (ref "C4") (pin "1") (pinfunction "1_1") (pintype "passive"))
      (node (ref "C5") (pin "1") (pinfunction "1_1") (pintype "passive"))
      (node (ref "C500") (pin "2") (pinfunction "2_2") (pintype "passive"))
      (node (ref "C501") (pin "1") (pinfunction "1_1") (pintype "passive"))
      (node (ref "C6") (pin "2") (pinfunction "2_2") (pintype "passive"))
      (node (ref "C7") (pin "1") (pinfunction "1_1") (pintype "passive"))
      (node (ref "C9") (pin "2") (pinfunction "2_2") (pintype "passive"))
      (node (ref "CV_A") (pin "P$1") (pinfunction "5_P$1") (pintype "passive"))
      (node (ref "CV_A") (pin "P$2") (pinfunction "4_P$2") (pintype "passive"))
      (node (ref "CV_B") (pin "P$1") (pinfunction "5_P$1") (pintype "passive"))
      (node (ref "CV_B") (pin "P$2") (pinfunction "4_P$2") (pintype "passive"))
      (node (ref "CV_C") (pin "P$1") (pinfunction "5_P$1") (pintype "passive"))
      (node (ref "CV_C") (pin "P$2") (pinfunction "4_P$2") (pintype "passive"))
      (node (ref "CV_D") (pin "P$1") (pinfunction "5_P$1") (pintype "passive"))
      (node (ref "CV_D") (pin "P$2") (pinfunction "4_P$2") (pintype "passive"))
      (node (ref "D500") (pin "1") (pinfunction "A1_1") (pintype "passive"))
      (node (ref "D600") (pin "1") (pinfunction "A1_1") (pintype "passive"))
      (node (ref "D700") (pin "1") (pinfunction "A1_1") (pintype "passive"))
      (node (ref "D800") (pin "1") (pinfunction "A1_1") (pintype "passive"))
      (node (ref "DAC1") (pin "P$1") (pinfunction "5_P$1") (pintype "passive"))
      (node (ref "DAC2") (pin "P$1") (pinfunction "5_P$1") (pintype "passive"))
      (node (ref "DAC3") (pin "P$1") (pinfunction "5_P$1") (pintype "passive"))
      (node (ref "DAC4") (pin "P$1") (pinfunction "5_P$1") (pintype "passive"))
      (node (ref "IC2") (pin "10") (pinfunction "+IN_10") (pintype "input"))
      (node (ref "IC2") (pin "12") (pinfunction "+IN_12") (pintype "input"))
      (node (ref "IC2") (pin "3") (pinfunction "+IN_3") (pintype "input"))
      (node (ref "IC2") (pin "5") (pinfunction "+IN_5") (pintype "input"))
      (node (ref "IC4") (pin "1") (pinfunction "C_1") (pintype "passive"))
      (node (ref "IC6") (pin "10") (pinfunction "+IN_10") (pintype "input"))
      (node (ref "IC6") (pin "12") (pinfunction "+IN_12") (pintype "input"))
      (node (ref "IC6") (pin "3") (pinfunction "+IN_3") (pintype "input"))
      (node (ref "IC6") (pin "5") (pinfunction "+IN_5") (pintype "input"))
      (node (ref "IN_L") (pin "P$1") (pinfunction "5_P$1") (pintype "passive"))
      (node (ref "IN_L") (pin "P$2") (pinfunction "4_P$2") (pintype "passive"))
      (node (ref "IN_R") (pin "P$1") (pinfunction "5_P$1") (pintype "passive"))
      (node (ref "JP2") (pin "20") (pinfunction "20_20") (pintype "passive"))
      (node (ref "OUT_L") (pin "P$1") (pinfunction "5_P$1") (pintype "passive"))
      (node (ref "OUT_R") (pin "P$1") (pinfunction "5_P$1") (pintype "passive"))
      (node (ref "POT5") (pin "3") (pinfunction "3_3") (pintype "bidirectional"))
      (node (ref "POT5") (pin "P$5") (pinfunction "P$1_P$5") (pintype "bidirectional"))
      (node (ref "POT5") (pin "P$6") (pinfunction "P$1_P$6") (pintype "bidirectional"))
      (node (ref "POT6") (pin "3") (pinfunction "3_3") (pintype "bidirectional"))
      (node (ref "POT6") (pin "P$5") (pinfunction "P$1_P$5") (pintype "bidirectional"))
      (node (ref "POT6") (pin "P$6") (pinfunction "P$1_P$6") (pintype "bidirectional"))
      (node (ref "POT7") (pin "3") (pinfunction "3_3") (pintype "bidirectional"))
      (node (ref "POT7") (pin "P$5") (pinfunction "P$1_P$5") (pintype "bidirectional"))
      (node (ref "POT7") (pin "P$6") (pinfunction "P$1_P$6") (pintype "bidirectional"))
      (node (ref "POT8") (pin "3") (pinfunction "3_3") (pintype "bidirectional"))
      (node (ref "POT8") (pin "P$5") (pinfunction "P$1_P$5") (pintype "bidirectional"))
      (node (ref "POT8") (pin "P$6") (pinfunction "P$1_P$6") (pintype "bidirectional"))
      (node (ref "PWR") (pin "3") (pinfunction "3_3") (pintype "passive"))
      (node (ref "PWR") (pin "4") (pinfunction "4_4") (pintype "passive"))
      (node (ref "PWR") (pin "5") (pinfunction "5_5") (pintype "passive"))
      (node (ref "PWR") (pin "6") (pinfunction "6_6") (pintype "passive"))
      (node (ref "PWR") (pin "7") (pinfunction "7_7") (pintype "passive"))
      (node (ref "PWR") (pin "8") (pinfunction "8_8") (pintype "passive"))
      (node (ref "Q1") (pin "1") (pinfunction "G_1") (pintype "passive"))
      (node (ref "Q2") (pin "1") (pinfunction "G_1") (pintype "passive"))
      (node (ref "Q3") (pin "2") (pinfunction "E_2") (pintype "passive"))
      (node (ref "Q901") (pin "2") (pinfunction "E_2") (pintype "passive"))
      (node (ref "R13") (pin "1") (pinfunction "1_1") (pintype "passive"))
      (node (ref "R21") (pin "1") (pinfunction "1_1") (pintype "passive"))
      (node (ref "R25") (pin "1") (pinfunction "1_1") (pintype "passive"))
      (node (ref "R300") (pin "1") (pinfunction "1_1") (pintype "passive"))
      (node (ref "R45") (pin "1") (pinfunction "1_1") (pintype "passive"))
      (node (ref "R49") (pin "1") (pinfunction "1_1") (pintype "passive"))
      (node (ref "R55") (pin "1") (pinfunction "1_1") (pintype "passive"))
      (node (ref "R6") (pin "2") (pinfunction "2_2") (pintype "passive"))
      (node (ref "R8") (pin "2") (pinfunction "2_2") (pintype "passive"))
      (node (ref "R905") (pin "1") (pinfunction "1_1") (pintype "passive"))
      (node (ref "SW1") (pin "P1") (pinfunction "P_P1") (pintype "passive"))
      (node (ref "SW1") (pin "P2") (pinfunction "P_P2") (pintype "passive"))
      (node (ref "SW2") (pin "P1") (pinfunction "P_P1") (pintype "passive"))
      (node (ref "SW2") (pin "P2") (pinfunction "P_P2") (pintype "passive"))
      (node (ref "T1") (pin "2") (pinfunction "E_2") (pintype "passive"))
      (node (ref "T2") (pin "2") (pinfunction "E_2") (pintype "passive"))
      (node (ref "TR_IN_1") (pin "P$1") (pinfunction "5_P$1") (pintype "passive"))
      (node (ref "TR_IN_1") (pin "P$2") (pinfunction "4_P$2") (pintype "passive"))
      (node (ref "TR_IN_2") (pin "P$1") (pinfunction "5_P$1") (pintype "passive"))
      (node (ref "TR_IN_2") (pin "P$2") (pinfunction "4_P$2") (pintype "passive"))
      (node (ref "TR_OUT_1") (pin "P$1") (pinfunction "5_P$1") (pintype "passive"))
      (node (ref "TR_OUT_2") (pin "P$1") (pinfunction "5_P$1") (pintype "passive"))
      (node (ref "U1") (pin "AUDIO_ING") (pinfunction "1_AUDIO_ING") (pintype "passive"))
      (node (ref "U1") (pin "P8_01") (pinfunction "P8_01-GND_P8_01") (pintype "power_in"))
      (node (ref "U1") (pin "P8_02") (pinfunction "P8_02-GND_P8_02") (pintype "power_in"))
      (node (ref "U1") (pin "P9_01") (pinfunction "P9_01-GND_P9_01") (pintype "power_in"))
      (node (ref "U1") (pin "P9_02") (pinfunction "P9_02-GND_P9_02") (pintype "power_in"))
      (node (ref "U2") (pin "4") (pinfunction "GND_4") (pintype "bidirectional"))
      (node (ref "U3") (pin "GND") (pinfunction "GND_GND") (pintype "power_in"))
    )
    (net (code "48") (name "Net-(C10-Pad1)") (class "Default")
      (node (ref "C10") (pin "1") (pinfunction "1_1") (pintype "passive"))
      (node (ref "R18") (pin "1") (pinfunction "1_1") (pintype "passive"))
      (node (ref "R21") (pin "2") (pinfunction "2_2") (pintype "passive"))
      (node (ref "R9") (pin "2") (pinfunction "2_2") (pintype "passive"))
    )
    (net (code "49") (name "Net-(C14-Pad1)") (class "Default")
      (node (ref "C14") (pin "1") (pinfunction "1_1") (pintype "passive"))
      (node (ref "R16") (pin "2") (pinfunction "2_2") (pintype "passive"))
      (node (ref "R17") (pin "1") (pinfunction "1_1") (pintype "passive"))
      (node (ref "R5") (pin "1") (pinfunction "1_1") (pintype "passive"))
    )
    (net (code "50") (name "Net-(C21-Pad1)") (class "Default")
      (node (ref "C21") (pin "1") (pinfunction "1_1") (pintype "passive"))
      (node (ref "R52") (pin "2") (pinfunction "2_2") (pintype "passive"))
      (node (ref "R54") (pin "1") (pinfunction "1_1") (pintype "passive"))
      (node (ref "R55") (pin "2") (pinfunction "2_2") (pintype "passive"))
    )
    (net (code "51") (name "Net-(C22-Pad1)") (class "Default")
      (node (ref "C22") (pin "1") (pinfunction "1_1") (pintype "passive"))
      (node (ref "R22") (pin "1") (pinfunction "1_1") (pintype "passive"))
      (node (ref "R51") (pin "2") (pinfunction "2_2") (pintype "passive"))
      (node (ref "R53") (pin "1") (pinfunction "1_1") (pintype "passive"))
    )
    (net (code "52") (name "Net-(CV_A-3)") (class "Default")
      (node (ref "CV_A") (pin "P$3") (pinfunction "3_P$3") (pintype "passive"))
      (node (ref "R501") (pin "1") (pinfunction "1_1") (pintype "passive"))
    )
    (net (code "53") (name "Net-(CV_B-3)") (class "Default")
      (node (ref "CV_B") (pin "P$3") (pinfunction "3_P$3") (pintype "passive"))
      (node (ref "R601") (pin "1") (pinfunction "1_1") (pintype "passive"))
    )
    (net (code "54") (name "Net-(CV_C-3)") (class "Default")
      (node (ref "CV_C") (pin "P$3") (pinfunction "3_P$3") (pintype "passive"))
      (node (ref "R701") (pin "1") (pinfunction "1_1") (pintype "passive"))
    )
    (net (code "55") (name "Net-(CV_D-3)") (class "Default")
      (node (ref "CV_D") (pin "P$3") (pinfunction "3_P$3") (pintype "passive"))
      (node (ref "R801") (pin "1") (pinfunction "1_1") (pintype "passive"))
    )
    (net (code "56") (name "Net-(D500-C1A2)") (class "Default")
      (node (ref "D500") (pin "3") (pinfunction "C1A2_3") (pintype "passive"))
      (node (ref "R504") (pin "1") (pinfunction "1_1") (pintype "passive"))
      (node (ref "R505") (pin "2") (pinfunction "2_2") (pintype "passive"))
    )
    (net (code "57") (name "Net-(D600-C1A2)") (class "Default")
      (node (ref "D600") (pin "3") (pinfunction "C1A2_3") (pintype "passive"))
      (node (ref "R604") (pin "1") (pinfunction "1_1") (pintype "passive"))
      (node (ref "R605") (pin "2") (pinfunction "2_2") (pintype "passive"))
    )
    (net (code "58") (name "Net-(D700-C1A2)") (class "Default")
      (node (ref "D700") (pin "3") (pinfunction "C1A2_3") (pintype "passive"))
      (node (ref "R704") (pin "1") (pinfunction "1_1") (pintype "passive"))
      (node (ref "R705") (pin "2") (pinfunction "2_2") (pintype "passive"))
    )
    (net (code "59") (name "Net-(D800-C1A2)") (class "Default")
      (node (ref "D800") (pin "3") (pinfunction "C1A2_3") (pintype "passive"))
      (node (ref "R804") (pin "1") (pinfunction "1_1") (pintype "passive"))
      (node (ref "R805") (pin "2") (pinfunction "2_2") (pintype "passive"))
    )
    (net (code "60") (name "Net-(DAC1-3)") (class "Default")
      (node (ref "DAC1") (pin "P$3") (pinfunction "3_P$3") (pintype "passive"))
      (node (ref "R27") (pin "2") (pinfunction "2_2") (pintype "passive"))
    )
    (net (code "61") (name "Net-(DAC2-3)") (class "Default")
      (node (ref "DAC2") (pin "P$3") (pinfunction "3_P$3") (pintype "passive"))
      (node (ref "R31") (pin "2") (pinfunction "2_2") (pintype "passive"))
    )
    (net (code "62") (name "Net-(DAC3-3)") (class "Default")
      (node (ref "DAC3") (pin "P$3") (pinfunction "3_P$3") (pintype "passive"))
      (node (ref "R35") (pin "2") (pinfunction "2_2") (pintype "passive"))
    )
    (net (code "63") (name "Net-(DAC4-3)") (class "Default")
      (node (ref "DAC4") (pin "P$3") (pinfunction "3_P$3") (pintype "passive"))
      (node (ref "R39") (pin "2") (pinfunction "2_2") (pintype "passive"))
    )
    (net (code "64") (name "Net-(IC1A-+IN)") (class "Default")
      (node (ref "IC1") (pin "3") (pinfunction "+IN_3") (pintype "input"))
      (node (ref "R18") (pin "2") (pinfunction "2_2") (pintype "passive"))
    )
    (net (code "65") (name "Net-(IC1A--IN)") (class "Default")
      (node (ref "C8") (pin "1") (pinfunction "1_1") (pintype "passive"))
      (node (ref "IC1") (pin "2") (pinfunction "-IN_2") (pintype "input"))
      (node (ref "R17") (pin "2") (pinfunction "2_2") (pintype "passive"))
    )
    (net (code "66") (name "Net-(IC1A-OUT)") (class "Default")
      (node (ref "C8") (pin "2") (pinfunction "2_2") (pintype "passive"))
      (node (ref "IC1") (pin "1") (pinfunction "OUT_1") (pintype "output"))
      (node (ref "R5") (pin "2") (pinfunction "2_2") (pintype "passive"))
      (node (ref "R7") (pin "1") (pinfunction "1_1") (pintype "passive"))
    )
    (net (code "67") (name "Net-(IC1B-+IN)") (class "Default")
      (node (ref "IC1") (pin "5") (pinfunction "+IN_5") (pintype "input"))
      (node (ref "R54") (pin "2") (pinfunction "2_2") (pintype "passive"))
    )
    (net (code "68") (name "Net-(IC1B--IN)") (class "Default")
      (node (ref "C15") (pin "1") (pinfunction "1_1") (pintype "passive"))
      (node (ref "IC1") (pin "6") (pinfunction "-IN_6") (pintype "input"))
      (node (ref "R53") (pin "2") (pinfunction "2_2") (pintype "passive"))
    )
    (net (code "69") (name "Net-(IC1B-OUT)") (class "Default")
      (node (ref "C15") (pin "2") (pinfunction "2_2") (pintype "passive"))
      (node (ref "IC1") (pin "7") (pinfunction "OUT_7") (pintype "output"))
      (node (ref "R22") (pin "2") (pinfunction "2_2") (pintype "passive"))
      (node (ref "R23") (pin "1") (pinfunction "1_1") (pintype "passive"))
    )
    (net (code "70") (name "Net-(IC2A--IN)") (class "Default")
      (node (ref "IC2") (pin "2") (pinfunction "-IN_2") (pintype "input"))
      (node (ref "R500") (pin "2") (pinfunction "2_2") (pintype "passive"))
      (node (ref "R501") (pin "2") (pinfunction "2_2") (pintype "passive"))
      (node (ref "R503") (pin "1") (pinfunction "1_1") (pintype "passive"))
    )
    (net (code "71") (name "Net-(IC2A-OUT)") (class "Default")
      (node (ref "IC2") (pin "1") (pinfunction "OUT_1") (pintype "output"))
      (node (ref "R503") (pin "2") (pinfunction "2_2") (pintype "passive"))
      (node (ref "R504") (pin "2") (pinfunction "2_2") (pintype "passive"))
    )
    (net (code "72") (name "Net-(IC2B--IN)") (class "Default")
      (node (ref "IC2") (pin "6") (pinfunction "-IN_6") (pintype "input"))
      (node (ref "R600") (pin "2") (pinfunction "2_2") (pintype "passive"))
      (node (ref "R601") (pin "2") (pinfunction "2_2") (pintype "passive"))
      (node (ref "R603") (pin "1") (pinfunction "1_1") (pintype "passive"))
    )
    (net (code "73") (name "Net-(IC2B-OUT)") (class "Default")
      (node (ref "IC2") (pin "7") (pinfunction "OUT_7") (pintype "output"))
      (node (ref "R603") (pin "2") (pinfunction "2_2") (pintype "passive"))
      (node (ref "R604") (pin "2") (pinfunction "2_2") (pintype "passive"))
    )
    (net (code "74") (name "Net-(IC2C--IN)") (class "Default")
      (node (ref "IC2") (pin "9") (pinfunction "-IN_9") (pintype "input"))
      (node (ref "R700") (pin "2") (pinfunction "2_2") (pintype "passive"))
      (node (ref "R701") (pin "2") (pinfunction "2_2") (pintype "passive"))
      (node (ref "R703") (pin "1") (pinfunction "1_1") (pintype "passive"))
    )
    (net (code "75") (name "Net-(IC2C-OUT)") (class "Default")
      (node (ref "IC2") (pin "8") (pinfunction "OUT_8") (pintype "output"))
      (node (ref "R703") (pin "2") (pinfunction "2_2") (pintype "passive"))
      (node (ref "R704") (pin "2") (pinfunction "2_2") (pintype "passive"))
    )
    (net (code "76") (name "Net-(IC2D--IN)") (class "Default")
      (node (ref "IC2") (pin "13") (pinfunction "-IN_13") (pintype "input"))
      (node (ref "R800") (pin "2") (pinfunction "2_2") (pintype "passive"))
      (node (ref "R801") (pin "2") (pinfunction "2_2") (pintype "passive"))
      (node (ref "R803") (pin "1") (pinfunction "1_1") (pintype "passive"))
    )
    (net (code "77") (name "Net-(IC2D-OUT)") (class "Default")
      (node (ref "IC2") (pin "14") (pinfunction "OUT_14") (pintype "output"))
      (node (ref "R803") (pin "2") (pinfunction "2_2") (pintype "passive"))
      (node (ref "R804") (pin "2") (pinfunction "2_2") (pintype "passive"))
    )
    (net (code "78") (name "Net-(IC5A-+IN)") (class "Default")
      (node (ref "IC5") (pin "3") (pinfunction "+IN_3") (pintype "input"))
      (node (ref "IN_L") (pin "P$3") (pinfunction "3_P$3") (pintype "passive"))
      (node (ref "IN_R") (pin "P$2") (pinfunction "4_P$2") (pintype "passive"))
      (node (ref "R300") (pin "2") (pinfunction "2_2") (pintype "passive"))
    )
    (net (code "79") (name "Net-(IC5A--IN)") (class "Default")
      (node (ref "IC5") (pin "1") (pinfunction "OUT_1") (pintype "output"))
      (node (ref "IC5") (pin "2") (pinfunction "-IN_2") (pintype "input"))
      (node (ref "R10") (pin "2") (pinfunction "2_2") (pintype "passive"))
    )
    (net (code "80") (name "Net-(IC5B-+IN)") (class "Default")
      (node (ref "IC5") (pin "5") (pinfunction "+IN_5") (pintype "input"))
      (node (ref "IN_R") (pin "P$3") (pinfunction "3_P$3") (pintype "passive"))
      (node (ref "R13") (pin "2") (pinfunction "2_2") (pintype "passive"))
    )
    (net (code "81") (name "Net-(IC5B--IN)") (class "Default")
      (node (ref "IC5") (pin "6") (pinfunction "-IN_6") (pintype "input"))
      (node (ref "IC5") (pin "7") (pinfunction "OUT_7") (pintype "output"))
      (node (ref "R11") (pin "2") (pinfunction "2_2") (pintype "passive"))
    )
    (net (code "82") (name "Net-(IC6A--IN)") (class "Default")
      (node (ref "C18") (pin "1") (pinfunction "1_1") (pintype "passive"))
      (node (ref "IC6") (pin "2") (pinfunction "-IN_2") (pintype "input"))
      (node (ref "R32") (pin "1") (pinfunction "1_1") (pintype "passive"))
      (node (ref "R33") (pin "1") (pinfunction "1_1") (pintype "passive"))
      (node (ref "R34") (pin "1") (pinfunction "1_1") (pintype "passive"))
    )
    (net (code "83") (name "Net-(IC6A-OUT)") (class "Default")
      (node (ref "C18") (pin "2") (pinfunction "2_2") (pintype "passive"))
      (node (ref "IC6") (pin "1") (pinfunction "OUT_1") (pintype "output"))
      (node (ref "R31") (pin "1") (pinfunction "1_1") (pintype "passive"))
      (node (ref "R33") (pin "2") (pinfunction "2_2") (pintype "passive"))
    )
    (net (code "84") (name "Net-(IC6B--IN)") (class "Default")
      (node (ref "C20") (pin "1") (pinfunction "1_1") (pintype "passive"))
      (node (ref "IC6") (pin "6") (pinfunction "-IN_6") (pintype "input"))
      (node (ref "R40") (pin "1") (pinfunction "1_1") (pintype "passive"))
      (node (ref "R41") (pin "1") (pinfunction "1_1") (pintype "passive"))
      (node (ref "R42") (pin "1") (pinfunction "1_1") (pintype "passive"))
    )
    (net (code "85") (name "Net-(IC6B-OUT)") (class "Default")
      (node (ref "C20") (pin "2") (pinfunction "2_2") (pintype "passive"))
      (node (ref "IC6") (pin "7") (pinfunction "OUT_7") (pintype "output"))
      (node (ref "R39") (pin "1") (pinfunction "1_1") (pintype "passive"))
      (node (ref "R41") (pin "2") (pinfunction "2_2") (pintype "passive"))
    )
    (net (code "86") (name "Net-(IC6C--IN)") (class "Default")
      (node (ref "C19") (pin "1") (pinfunction "1_1") (pintype "passive"))
      (node (ref "IC6") (pin "9") (pinfunction "-IN_9") (pintype "input"))
      (node (ref "R36") (pin "1") (pinfunction "1_1") (pintype "passive"))
      (node (ref "R37") (pin "1") (pinfunction "1_1") (pintype "passive"))
      (node (ref "R38") (pin "1") (pinfunction "1_1") (pintype "passive"))
    )
    (net (code "87") (name "Net-(IC6C-OUT)") (class "Default")
      (node (ref "C19") (pin "2") (pinfunction "2_2") (pintype "passive"))
      (node (ref "IC6") (pin "8") (pinfunction "OUT_8") (pintype "output"))
      (node (ref "R35") (pin "1") (pinfunction "1_1") (pintype "passive"))
      (node (ref "R37") (pin "2") (pinfunction "2_2") (pintype "passive"))
    )
    (net (code "88") (name "Net-(IC6D--IN)") (class "Default")
      (node (ref "C16") (pin "1") (pinfunction "1_1") (pintype "passive"))
      (node (ref "IC6") (pin "13") (pinfunction "-IN_13") (pintype "input"))
      (node (ref "R28") (pin "1") (pinfunction "1_1") (pintype "passive"))
      (node (ref "R29") (pin "1") (pinfunction "1_1") (pintype "passive"))
      (node (ref "R30") (pin "1") (pinfunction "1_1") (pintype "passive"))
    )
    (net (code "89") (name "Net-(IC6D-OUT)") (class "Default")
      (node (ref "C16") (pin "2") (pinfunction "2_2") (pintype "passive"))
      (node (ref "IC6") (pin "14") (pinfunction "OUT_14") (pintype "output"))
      (node (ref "R27") (pin "1") (pinfunction "1_1") (pintype "passive"))
      (node (ref "R29") (pin "2") (pinfunction "2_2") (pintype "passive"))
    )
    (net (code "90") (name "Net-(POT5-Pad2)") (class "Default")
      (node (ref "POT5") (pin "2") (pinfunction "2_2") (pintype "bidirectional"))
      (node (ref "R500") (pin "1") (pinfunction "1_1") (pintype "passive"))
    )
    (net (code "91") (name "Net-(POT6-Pad2)") (class "Default")
      (node (ref "POT6") (pin "2") (pinfunction "2_2") (pintype "bidirectional"))
      (node (ref "R600") (pin "1") (pinfunction "1_1") (pintype "passive"))
    )
    (net (code "92") (name "Net-(POT7-Pad2)") (class "Default")
      (node (ref "POT7") (pin "2") (pinfunction "2_2") (pintype "bidirectional"))
      (node (ref "R700") (pin "1") (pinfunction "1_1") (pintype "passive"))
    )
    (net (code "93") (name "Net-(POT8-Pad2)") (class "Default")
      (node (ref "POT8") (pin "2") (pinfunction "2_2") (pintype "bidirectional"))
      (node (ref "R800") (pin "1") (pinfunction "1_1") (pintype "passive"))
    )
    (net (code "94") (name "Net-(Q1-D)") (class "Default")
      (node (ref "PWR") (pin "1") (pinfunction "1_1") (pintype "passive"))
      (node (ref "PWR") (pin "2") (pinfunction "2_2") (pintype "passive"))
      (node (ref "Q1") (pin "3") (pinfunction "D_3") (pintype "passive"))
    )
    (net (code "95") (name "Net-(Q2-D)") (class "Default")
      (node (ref "PWR") (pin "10") (pinfunction "10_10") (pintype "passive"))
      (node (ref "PWR") (pin "9") (pinfunction "9_9") (pintype "passive"))
      (node (ref "Q2") (pin "3") (pinfunction "D_3") (pintype "passive"))
    )
    (net (code "96") (name "Net-(Q3-B)") (class "Default")
      (node (ref "Q3") (pin "1") (pinfunction "B_1") (pintype "passive"))
      (node (ref "R24") (pin "2") (pinfunction "2_2") (pintype "passive"))
      (node (ref "R25") (pin "2") (pinfunction "2_2") (pintype "passive"))
    )
    (net (code "97") (name "Net-(Q901-B)") (class "Default")
      (node (ref "Q901") (pin "1") (pinfunction "B_1") (pintype "passive"))
      (node (ref "R904") (pin "2") (pinfunction "2_2") (pintype "passive"))
      (node (ref "R905") (pin "2") (pinfunction "2_2") (pintype "passive"))
    )
    (net (code "98") (name "Net-(SW1B-C)") (class "Default")
      (node (ref "R3") (pin "2") (pinfunction "2_2") (pintype "passive"))
      (node (ref "SW1") (pin "PL2") (pinfunction "C_PL2") (pintype "passive"))
    )
    (net (code "99") (name "Net-(SW2B-C)") (class "Default")
      (node (ref "R4") (pin "2") (pinfunction "2_2") (pintype "passive"))
      (node (ref "SW2") (pin "PL2") (pinfunction "C_PL2") (pintype "passive"))
    )
    (net (code "100") (name "Net-(T1-B)") (class "Default")
      (node (ref "R43") (pin "2") (pinfunction "2_2") (pintype "passive"))
      (node (ref "T1") (pin "1") (pinfunction "B_1") (pintype "passive"))
    )
    (net (code "101") (name "Net-(T1-C)") (class "Default")
      (node (ref "R44") (pin "1") (pinfunction "1_1") (pintype "passive"))
      (node (ref "R46") (pin "2") (pinfunction "2_2") (pintype "passive"))
      (node (ref "T1") (pin "3") (pinfunction "C_3") (pintype "passive"))
    )
    (net (code "102") (name "Net-(T2-B)") (class "Default")
      (node (ref "R47") (pin "2") (pinfunction "2_2") (pintype "passive"))
      (node (ref "T2") (pin "1") (pinfunction "B_1") (pintype "passive"))
    )
    (net (code "103") (name "Net-(T2-C)") (class "Default")
      (node (ref "R48") (pin "1") (pinfunction "1_1") (pintype "passive"))
      (node (ref "R50") (pin "2") (pinfunction "2_2") (pintype "passive"))
      (node (ref "T2") (pin "3") (pinfunction "C_3") (pintype "passive"))
    )
    (net (code "104") (name "Net-(TR_IN_1-3)") (class "Default")
      (node (ref "R904") (pin "1") (pinfunction "1_1") (pintype "passive"))
      (node (ref "TR_IN_1") (pin "P$3") (pinfunction "3_P$3") (pintype "passive"))
    )
    (net (code "105") (name "Net-(TR_IN_2-3)") (class "Default")
      (node (ref "R24") (pin "1") (pinfunction "1_1") (pintype "passive"))
      (node (ref "TR_IN_2") (pin "P$3") (pinfunction "3_P$3") (pintype "passive"))
    )
    (net (code "106") (name "Net-(TR_OUT_1-3)") (class "Default")
      (node (ref "R44") (pin "2") (pinfunction "2_2") (pintype "passive"))
      (node (ref "R45") (pin "2") (pinfunction "2_2") (pintype "passive"))
      (node (ref "TR_OUT_1") (pin "P$3") (pinfunction "3_P$3") (pintype "passive"))
    )
    (net (code "107") (name "Net-(TR_OUT_2-3)") (class "Default")
      (node (ref "R48") (pin "2") (pinfunction "2_2") (pintype "passive"))
      (node (ref "R49") (pin "2") (pinfunction "2_2") (pintype "passive"))
      (node (ref "TR_OUT_2") (pin "P$3") (pinfunction "3_P$3") (pintype "passive"))
    )
    (net (code "108") (name "Net-(U1E-P9_05-VDD_5V)") (class "Default")
      (node (ref "JP1") (pin "2") (pinfunction "2_2") (pintype "passive"))
      (node (ref "U1") (pin "P9_05") (pinfunction "P9_05-VDD_5V_P9_05") (pintype "power_in"))
      (node (ref "U1") (pin "P9_06") (pinfunction "P9_06-VDD_5V_P9_06") (pintype "power_in"))
    )
    (net (code "109") (name "Net-(U2-VDD)") (class "Default")
      (node (ref "C25") (pin "2") (pinfunction "2_2") (pintype "passive"))
      (node (ref "SJ1") (pin "2") (pinfunction "2_2") (pintype "passive"))
      (node (ref "U2") (pin "2") (pinfunction "VDD_2") (pintype "bidirectional"))
    )
    (net (code "110") (name "Net-(USBD-Pad1)") (class "Default")
      (node (ref "USBD") (pin "1") (pinfunction "1_1") (pintype "passive"))
      (node (ref "X1") (pin "GND") (pinfunction "GND_GND") (pintype "bidirectional"))
    )
    (net (code "111") (name "Net-(USBD-Pad2)") (class "Default")
      (node (ref "USBD") (pin "2") (pinfunction "2_2") (pintype "passive"))
      (node (ref "X1") (pin "VBUS") (pinfunction "VBUS_VBUS") (pintype "bidirectional"))
    )
    (net (code "112") (name "Net-(USBD-Pad3)") (class "Default")
      (node (ref "USBD") (pin "3") (pinfunction "3_3") (pintype "passive"))
      (node (ref "X1") (pin "D-") (pinfunction "D-_D-") (pintype "bidirectional"))
    )
    (net (code "113") (name "Net-(USBD-Pad4)") (class "Default")
      (node (ref "USBD") (pin "4") (pinfunction "4_4") (pintype "passive"))
      (node (ref "X1") (pin "D+") (pinfunction "D+_D+") (pintype "bidirectional"))
    )
    (net (code "114") (name "unconnected-(DAC1-4-PadP$2)") (class "Default")
      (node (ref "DAC1") (pin "P$2") (pinfunction "4_P$2") (pintype "passive"))
    )
    (net (code "115") (name "unconnected-(DAC2-4-PadP$2)") (class "Default")
      (node (ref "DAC2") (pin "P$2") (pinfunction "4_P$2") (pintype "passive"))
    )
    (net (code "116") (name "unconnected-(DAC3-4-PadP$2)") (class "Default")
      (node (ref "DAC3") (pin "P$2") (pinfunction "4_P$2") (pintype "passive"))
    )
    (net (code "117") (name "unconnected-(DAC4-4-PadP$2)") (class "Default")
      (node (ref "DAC4") (pin "P$2") (pinfunction "4_P$2") (pintype "passive"))
    )
    (net (code "118") (name "unconnected-(OUT_L-4-PadP$2)") (class "Default")
      (node (ref "OUT_L") (pin "P$2") (pinfunction "4_P$2") (pintype "passive"))
    )
    (net (code "119") (name "unconnected-(OUT_R-4-PadP$2)") (class "Default")
      (node (ref "OUT_R") (pin "P$2") (pinfunction "4_P$2") (pintype "passive"))
    )
    (net (code "120") (name "unconnected-(TR_OUT_1-4-PadP$2)") (class "Default")
      (node (ref "TR_OUT_1") (pin "P$2") (pinfunction "4_P$2") (pintype "passive"))
    )
    (net (code "121") (name "unconnected-(TR_OUT_2-4-PadP$2)") (class "Default")
      (node (ref "TR_OUT_2") (pin "P$2") (pinfunction "4_P$2") (pintype "passive"))
    )
    (net (code "122") (name "unconnected-(U1E-P8_03-GPIO1_6-PadP8_03)") (class "Default")
      (node (ref "U1") (pin "P8_03") (pinfunction "P8_03-GPIO1_6_P8_03") (pintype "passive"))
    )
    (net (code "123") (name "unconnected-(U1E-P8_04-GPIO1_7-PadP8_04)") (class "Default")
      (node (ref "U1") (pin "P8_04") (pinfunction "P8_04-GPIO1_7_P8_04") (pintype "passive"))
    )
    (net (code "124") (name "unconnected-(U1E-P8_05-GPIO1_2-PadP8_05)") (class "Default")
      (node (ref "U1") (pin "P8_05") (pinfunction "P8_05-GPIO1_2_P8_05") (pintype "passive"))
    )
    (net (code "125") (name "unconnected-(U1E-P8_06-GPIO1_3-PadP8_06)") (class "Default")
      (node (ref "U1") (pin "P8_06") (pinfunction "P8_06-GPIO1_3_P8_06") (pintype "passive"))
    )
    (net (code "126") (name "unconnected-(U1E-P9_08-SYS_5V-PadP9_08)") (class "Default")
      (node (ref "U1") (pin "P9_08") (pinfunction "P9_08-SYS_5V_P9_08") (pintype "passive"))
    )
    (net (code "127") (name "unconnected-(U1E-P9_09-PWR_BUT-PadP9_09)") (class "Default")
      (node (ref "U1") (pin "P9_09") (pinfunction "P9_09-PWR_BUT_P9_09") (pintype "passive"))
    )
    (net (code "128") (name "unconnected-(U1E-P9_10-SYS_RESETN-PadP9_10)") (class "Default")
      (node (ref "U1") (pin "P9_10") (pinfunction "P9_10-SYS_RESETN_P9_10") (pintype "passive"))
    )
    (net (code "129") (name "unconnected-(U1E-P9_11-UART4_RXD-PadP9_11)") (class "Default")
      (node (ref "U1") (pin "P9_11") (pinfunction "P9_11-UART4_RXD_P9_11") (pintype "passive"))
    )
    (net (code "130") (name "unconnected-(U1E-P9_13-UART4_TXD-PadP9_13)") (class "Default")
      (node (ref "U1") (pin "P9_13") (pinfunction "P9_13-UART4_TXD_P9_13") (pintype "passive"))
    )
    (net (code "131") (name "unconnected-(U1E-P9_15-GPIO1_16-PadP9_15)") (class "Default")
      (node (ref "U1") (pin "P9_15") (pinfunction "P9_15-GPIO1_16_P9_15") (pintype "passive"))
    )
    (net (code "132") (name "unconnected-(U1E-P9_16-EHRPWM1B-PadP9_16)") (class "Default")
      (node (ref "U1") (pin "P9_16") (pinfunction "P9_16-EHRPWM1B_P9_16") (pintype "passive"))
    )
  )
)
